# haasoscope_pro_fpga_board_-_start_of_io.net
KiCad netlist of a schematic drawn in EAGLE
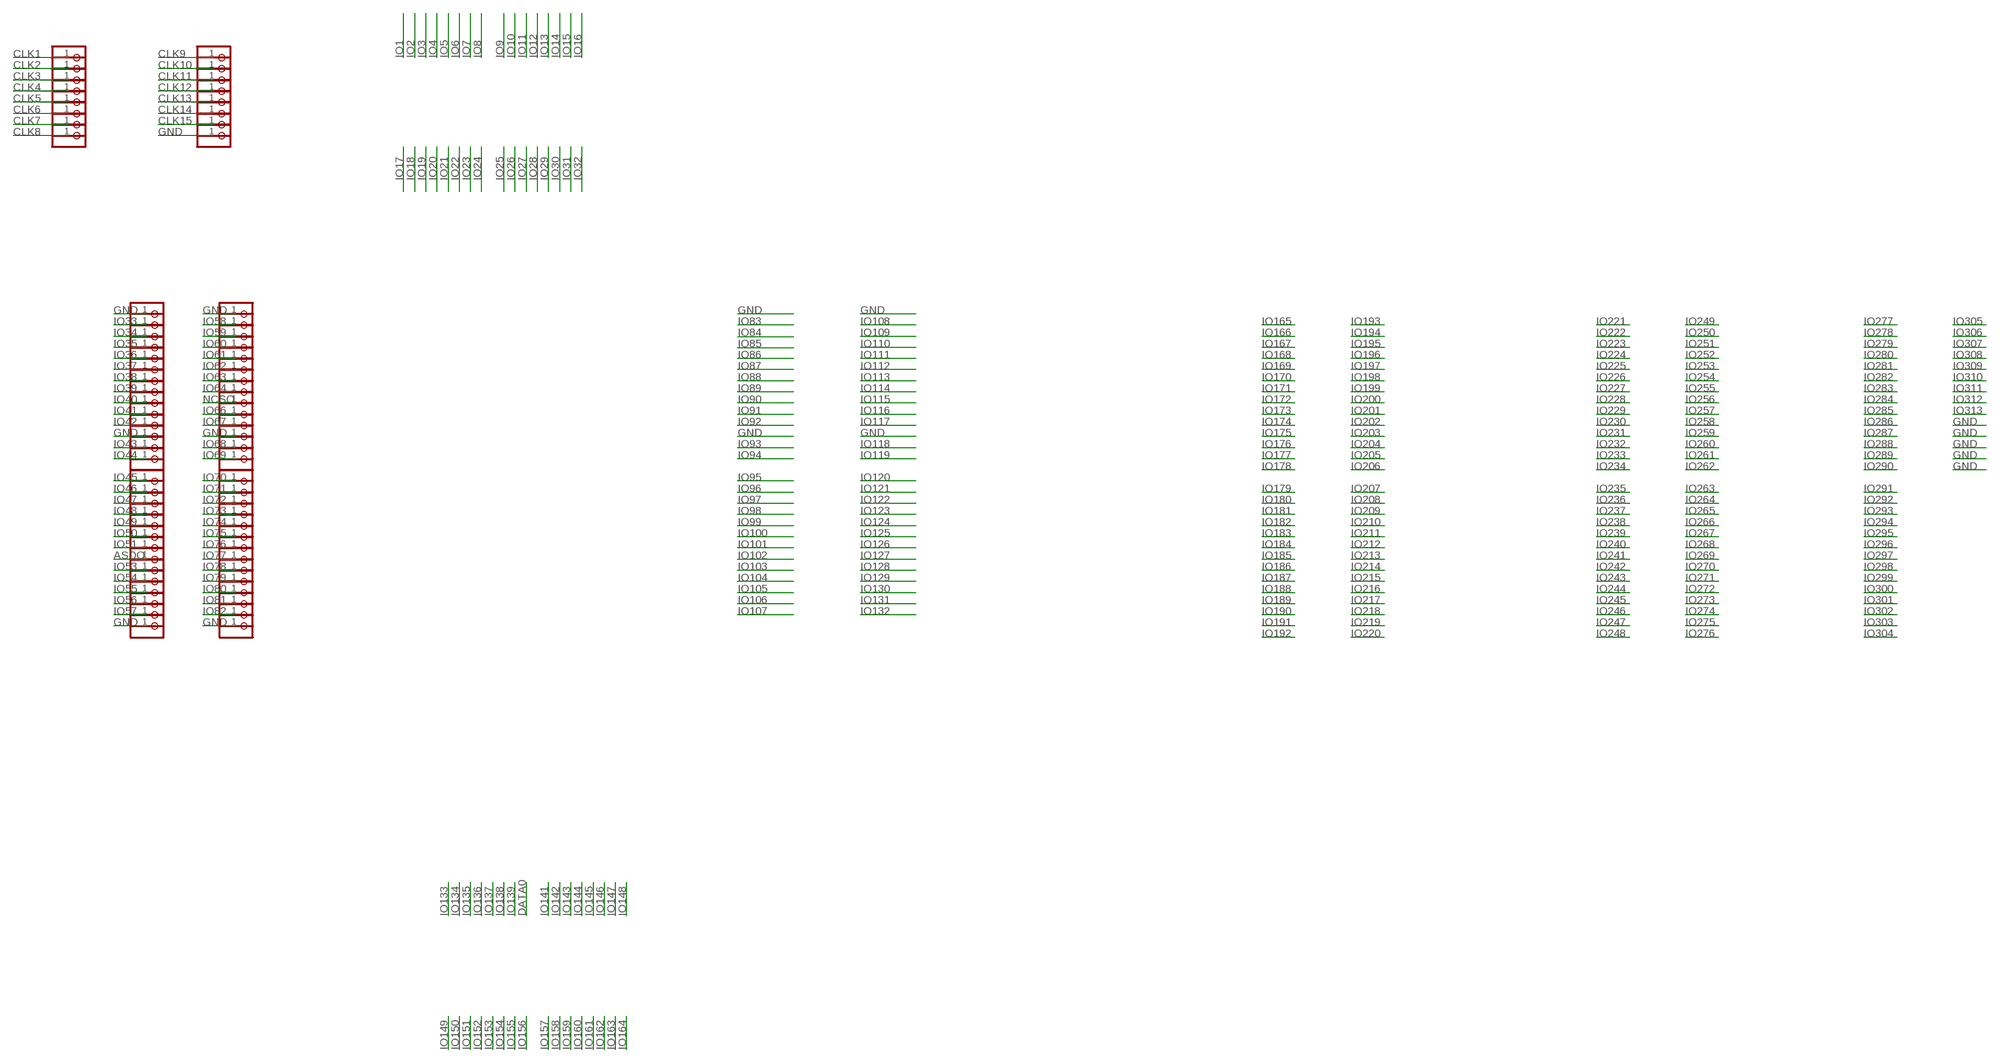
[diagram p0: schematic, sheet 1]
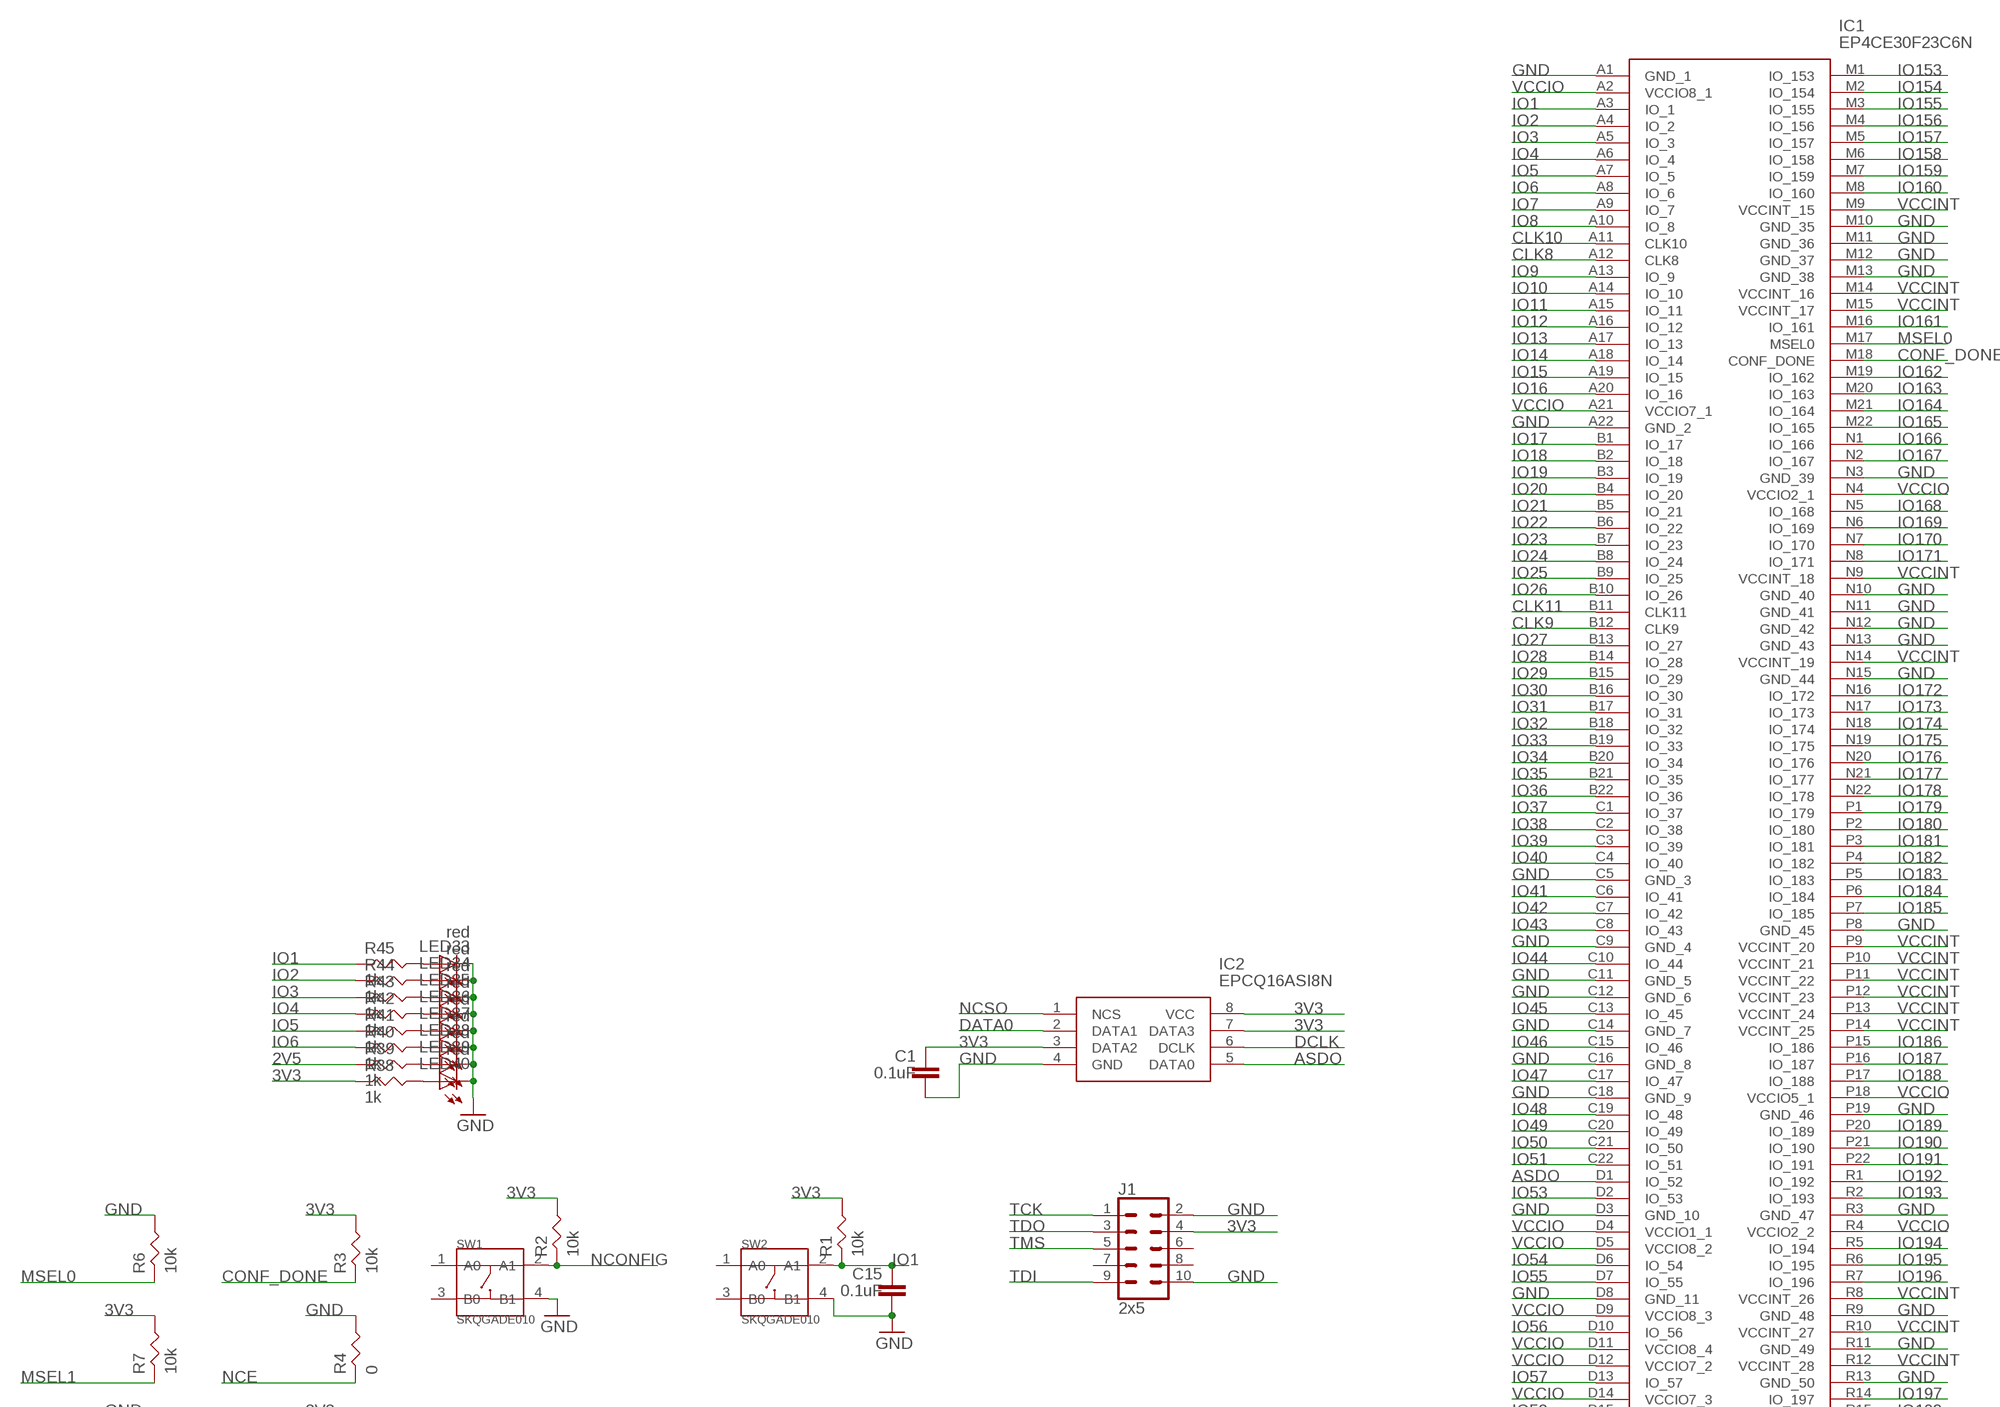
[diagram p1: schematic, sheet 2, part 1 of 2]
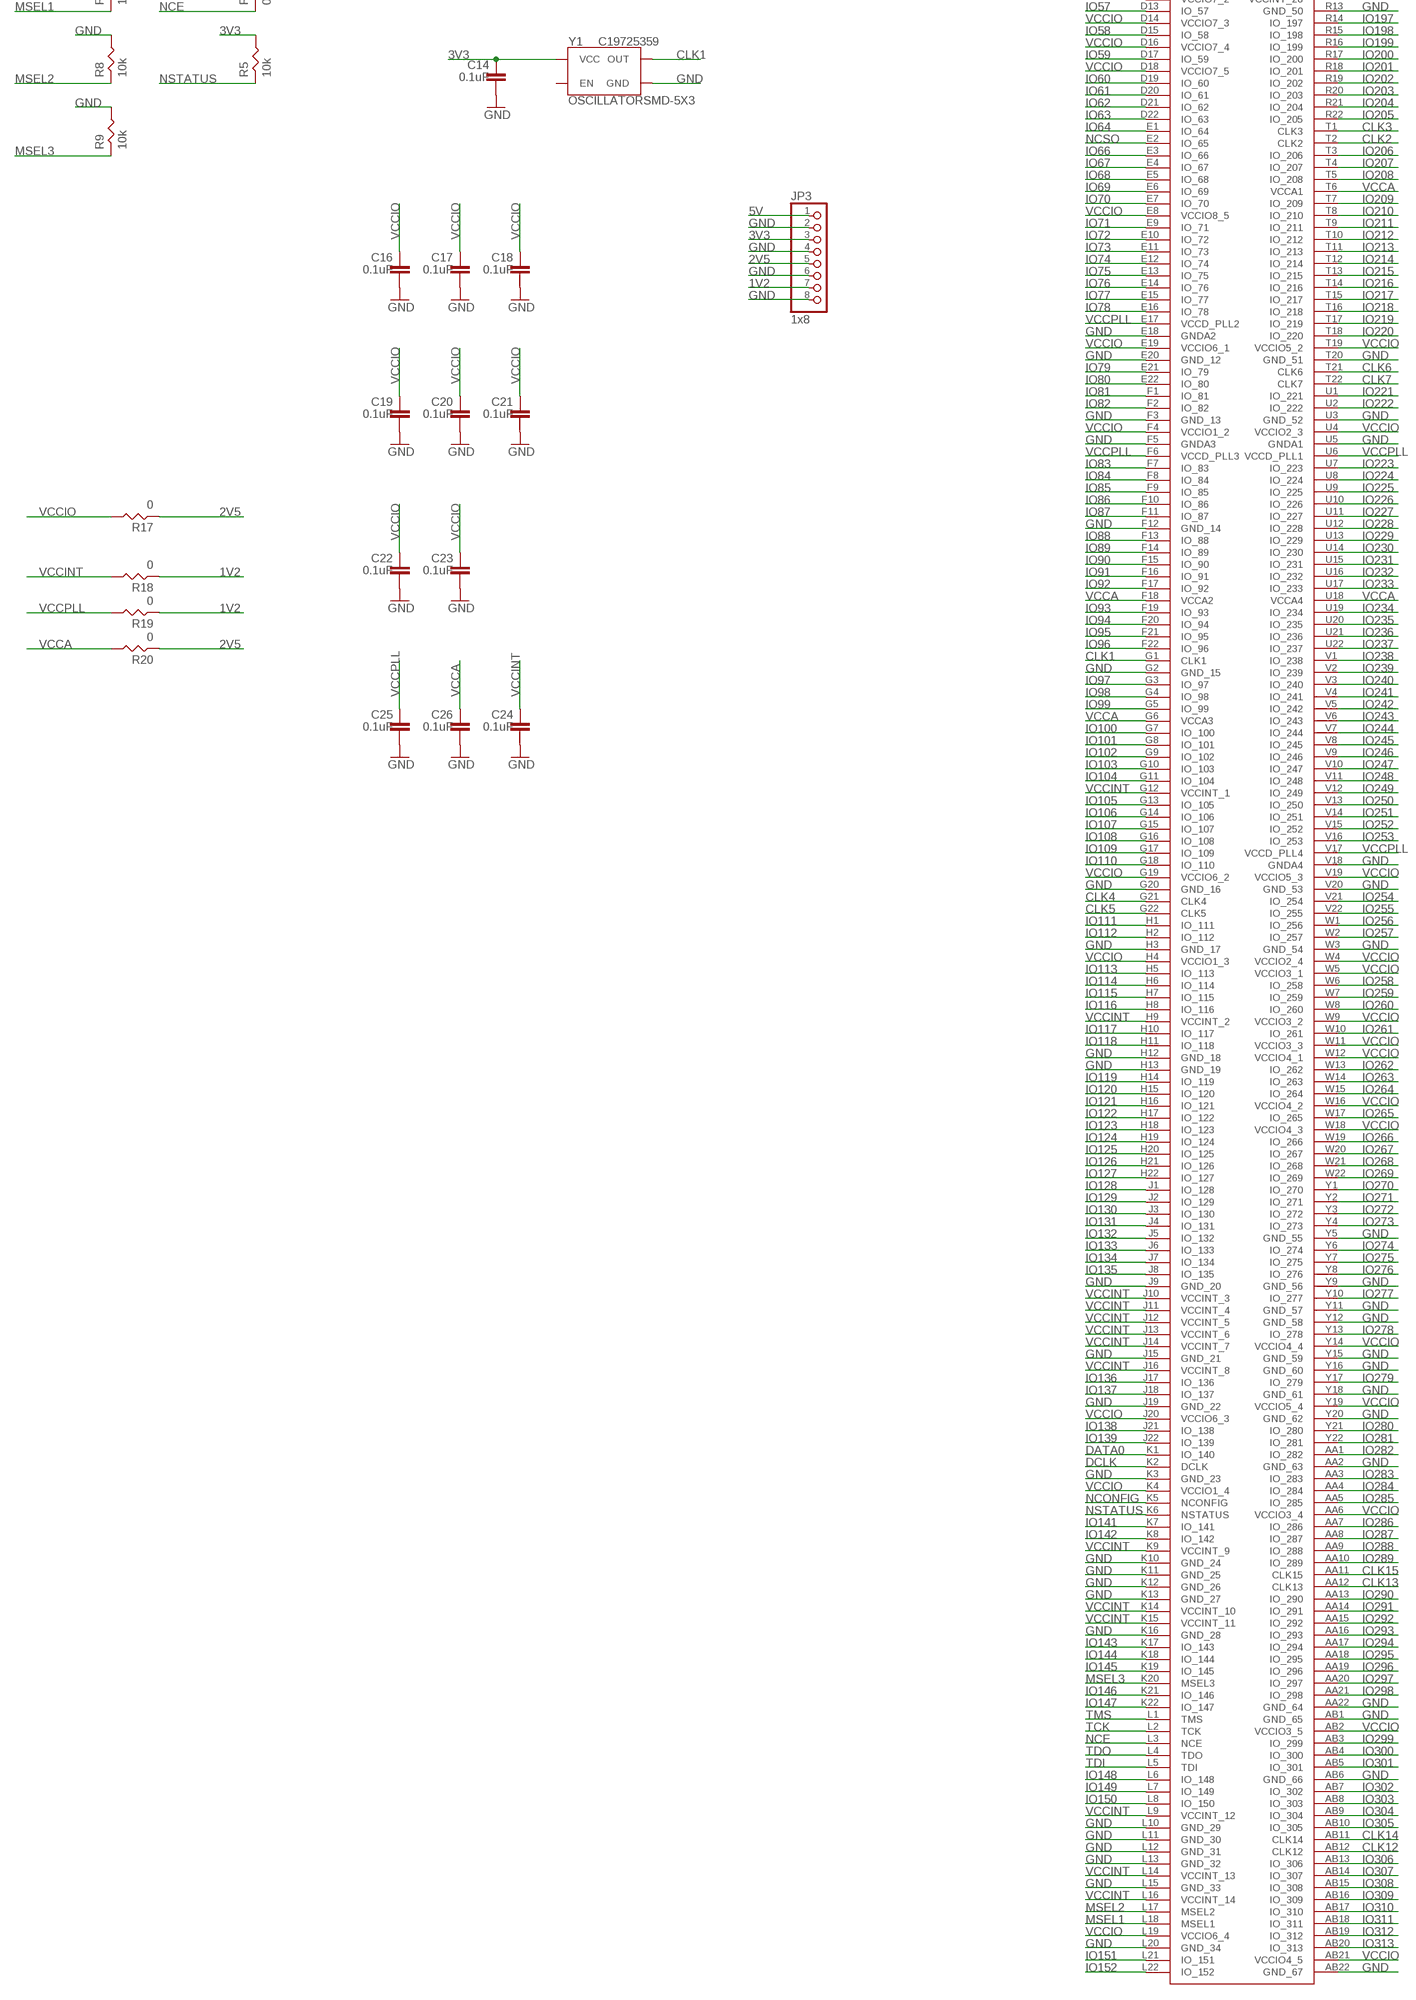
[diagram p2: schematic, sheet 2, part 2 of 2]
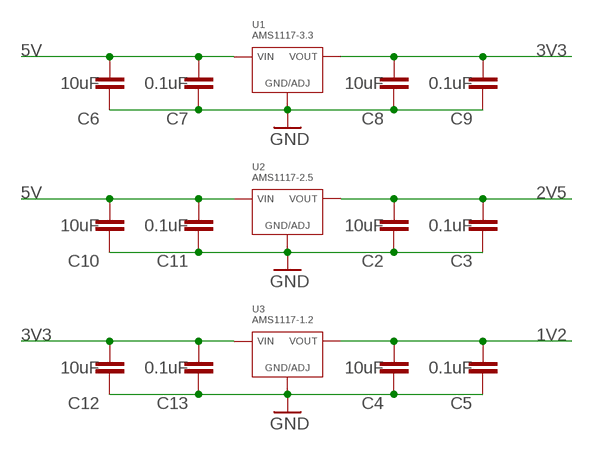
[diagram p3: schematic, sheet 3]

(export (version "E")
  (design (tool "Eeschema 10.0.6"))
  (components
    (comp (ref "C2")
      (value "10uF")
      (footprint "eagle-import:RESC0805_N")
      (libsource (lib "eagle-import") (part "CAPACITOR_0805_N"))
    )
    (comp (ref "C3")
      (value "0.1uF")
      (footprint "eagle-import:RESC0402_N")
      (libsource (lib "eagle-import") (part "CAPACITOR_0402_N"))
    )
    (comp (ref "C4")
      (value "10uF")
      (footprint "eagle-import:RESC0805_N")
      (libsource (lib "eagle-import") (part "CAPACITOR_0805_N"))
    )
    (comp (ref "C5")
      (value "0.1uF")
      (footprint "eagle-import:RESC0402_N")
      (libsource (lib "eagle-import") (part "CAPACITOR_0402_N"))
    )
    (comp (ref "C6")
      (value "10uF")
      (footprint "eagle-import:RESC0805_N")
      (libsource (lib "eagle-import") (part "CAPACITOR_0805_N"))
    )
    (comp (ref "C7")
      (value "0.1uF")
      (footprint "eagle-import:RESC0402_N")
      (libsource (lib "eagle-import") (part "CAPACITOR_0402_N"))
    )
    (comp (ref "C8")
      (value "10uF")
      (footprint "eagle-import:RESC0805_N")
      (libsource (lib "eagle-import") (part "CAPACITOR_0805_N"))
    )
    (comp (ref "C9")
      (value "0.1uF")
      (footprint "eagle-import:RESC0402_N")
      (libsource (lib "eagle-import") (part "CAPACITOR_0402_N"))
    )
    (comp (ref "C10")
      (value "10uF")
      (footprint "eagle-import:RESC0805_N")
      (libsource (lib "eagle-import") (part "CAPACITOR_0805_N"))
    )
    (comp (ref "C11")
      (value "0.1uF")
      (footprint "eagle-import:RESC0402_N")
      (libsource (lib "eagle-import") (part "CAPACITOR_0402_N"))
    )
    (comp (ref "C12")
      (value "10uF")
      (footprint "eagle-import:RESC0805_N")
      (libsource (lib "eagle-import") (part "CAPACITOR_0805_N"))
    )
    (comp (ref "C13")
      (value "0.1uF")
      (footprint "eagle-import:RESC0402_N")
      (libsource (lib "eagle-import") (part "CAPACITOR_0402_N"))
    )
    (comp (ref "U1")
      (value "AMS1117-3.3")
      (footprint "eagle-import:SOT-223-3")
      (fields
        (field (name "HOUSEPART") "NO")
        (field (name "MPN") "NCP1117LPST33T3G")
        (field (name "MPN_1") "AMS1117-3.3")
      )
      (libsource (lib "eagle-import") (part "NCP1117LPST33T3G"))
    )
    (comp (ref "U2")
      (value "AMS1117-2.5")
      (footprint "eagle-import:SOT-223-3")
      (fields
        (field (name "HOUSEPART") "NO")
        (field (name "MPN") "NCP1117LPST33T3G")
        (field (name "MPN_1") "AMS1117-2.5")
      )
      (libsource (lib "eagle-import") (part "NCP1117LPST33T3G"))
    )
    (comp (ref "U3")
      (value "AMS1117-1.2")
      (footprint "eagle-import:SOT-223-3")
      (fields
        (field (name "HOUSEPART") "NO")
        (field (name "MPN") "NCP1117LPST33T3G")
        (field (name "MPN_1") "AMS1117-1.2")
      )
      (libsource (lib "eagle-import") (part "NCP1117LPST33T3G"))
    )
    (comp (ref "JP1")
      (value "1")
      (footprint "eagle-import:1X01")
      (libsource (lib "eagle-import") (part "PINHD-1X1"))
    )
    (comp (ref "JP2")
      (value "1")
      (footprint "eagle-import:1X01")
      (libsource (lib "eagle-import") (part "PINHD-1X1"))
    )
    (comp (ref "JP4")
      (value "1")
      (footprint "eagle-import:1X01")
      (libsource (lib "eagle-import") (part "PINHD-1X1"))
    )
    (comp (ref "JP5")
      (value "1")
      (footprint "eagle-import:1X01")
      (libsource (lib "eagle-import") (part "PINHD-1X1"))
    )
    (comp (ref "JP6")
      (value "1")
      (footprint "eagle-import:1X01")
      (libsource (lib "eagle-import") (part "PINHD-1X1"))
    )
    (comp (ref "JP7")
      (value "1")
      (footprint "eagle-import:1X01")
      (libsource (lib "eagle-import") (part "PINHD-1X1"))
    )
    (comp (ref "JP8")
      (value "1")
      (footprint "eagle-import:1X01")
      (libsource (lib "eagle-import") (part "PINHD-1X1"))
    )
    (comp (ref "JP9")
      (value "1")
      (footprint "eagle-import:1X01")
      (libsource (lib "eagle-import") (part "PINHD-1X1"))
    )
    (comp (ref "JP10")
      (value "1")
      (footprint "eagle-import:1X01")
      (libsource (lib "eagle-import") (part "PINHD-1X1"))
    )
    (comp (ref "JP11")
      (value "1")
      (footprint "eagle-import:1X01")
      (libsource (lib "eagle-import") (part "PINHD-1X1"))
    )
    (comp (ref "JP12")
      (value "1")
      (footprint "eagle-import:1X01")
      (libsource (lib "eagle-import") (part "PINHD-1X1"))
    )
    (comp (ref "JP13")
      (value "1")
      (footprint "eagle-import:1X01")
      (libsource (lib "eagle-import") (part "PINHD-1X1"))
    )
    (comp (ref "JP14")
      (value "1")
      (footprint "eagle-import:1X01")
      (libsource (lib "eagle-import") (part "PINHD-1X1"))
    )
    (comp (ref "JP15")
      (value "1")
      (footprint "eagle-import:1X01")
      (libsource (lib "eagle-import") (part "PINHD-1X1"))
    )
    (comp (ref "JP16")
      (value "1")
      (footprint "eagle-import:1X01")
      (libsource (lib "eagle-import") (part "PINHD-1X1"))
    )
    (comp (ref "JP17")
      (value "1")
      (footprint "eagle-import:1X01")
      (libsource (lib "eagle-import") (part "PINHD-1X1"))
    )
    (comp (ref "JP18")
      (value "1")
      (footprint "eagle-import:1X01")
      (libsource (lib "eagle-import") (part "PINHD-1X1"))
    )
    (comp (ref "JP19")
      (value "1")
      (footprint "eagle-import:1X01")
      (libsource (lib "eagle-import") (part "PINHD-1X1"))
    )
    (comp (ref "JP20")
      (value "1")
      (footprint "eagle-import:1X01")
      (libsource (lib "eagle-import") (part "PINHD-1X1"))
    )
    (comp (ref "JP21")
      (value "1")
      (footprint "eagle-import:1X01")
      (libsource (lib "eagle-import") (part "PINHD-1X1"))
    )
    (comp (ref "JP22")
      (value "1")
      (footprint "eagle-import:1X01")
      (libsource (lib "eagle-import") (part "PINHD-1X1"))
    )
    (comp (ref "JP23")
      (value "1")
      (footprint "eagle-import:1X01")
      (libsource (lib "eagle-import") (part "PINHD-1X1"))
    )
    (comp (ref "JP24")
      (value "1")
      (footprint "eagle-import:1X01")
      (libsource (lib "eagle-import") (part "PINHD-1X1"))
    )
    (comp (ref "JP25")
      (value "1")
      (footprint "eagle-import:1X01")
      (libsource (lib "eagle-import") (part "PINHD-1X1"))
    )
    (comp (ref "JP26")
      (value "1")
      (footprint "eagle-import:1X01")
      (libsource (lib "eagle-import") (part "PINHD-1X1"))
    )
    (comp (ref "JP27")
      (value "1")
      (footprint "eagle-import:1X01")
      (libsource (lib "eagle-import") (part "PINHD-1X1"))
    )
    (comp (ref "JP28")
      (value "1")
      (footprint "eagle-import:1X01")
      (libsource (lib "eagle-import") (part "PINHD-1X1"))
    )
    (comp (ref "JP29")
      (value "1")
      (footprint "eagle-import:1X01")
      (libsource (lib "eagle-import") (part "PINHD-1X1"))
    )
    (comp (ref "JP30")
      (value "1")
      (footprint "eagle-import:1X01")
      (libsource (lib "eagle-import") (part "PINHD-1X1"))
    )
    (comp (ref "JP31")
      (value "1")
      (footprint "eagle-import:1X01")
      (libsource (lib "eagle-import") (part "PINHD-1X1"))
    )
    (comp (ref "JP32")
      (value "1")
      (footprint "eagle-import:1X01")
      (libsource (lib "eagle-import") (part "PINHD-1X1"))
    )
    (comp (ref "JP33")
      (value "1")
      (footprint "eagle-import:1X01")
      (libsource (lib "eagle-import") (part "PINHD-1X1"))
    )
    (comp (ref "JP34")
      (value "1")
      (footprint "eagle-import:1X01")
      (libsource (lib "eagle-import") (part "PINHD-1X1"))
    )
    (comp (ref "JP35")
      (value "1")
      (footprint "eagle-import:1X01")
      (libsource (lib "eagle-import") (part "PINHD-1X1"))
    )
    (comp (ref "JP36")
      (value "1")
      (footprint "eagle-import:1X01")
      (libsource (lib "eagle-import") (part "PINHD-1X1"))
    )
    (comp (ref "JP37")
      (value "1")
      (footprint "eagle-import:1X01")
      (libsource (lib "eagle-import") (part "PINHD-1X1"))
    )
    (comp (ref "JP38")
      (value "1")
      (footprint "eagle-import:1X01")
      (libsource (lib "eagle-import") (part "PINHD-1X1"))
    )
    (comp (ref "JP39")
      (value "1")
      (footprint "eagle-import:1X01")
      (libsource (lib "eagle-import") (part "PINHD-1X1"))
    )
    (comp (ref "JP40")
      (value "1")
      (footprint "eagle-import:1X01")
      (libsource (lib "eagle-import") (part "PINHD-1X1"))
    )
    (comp (ref "JP41")
      (value "1")
      (footprint "eagle-import:1X01")
      (libsource (lib "eagle-import") (part "PINHD-1X1"))
    )
    (comp (ref "JP42")
      (value "1")
      (footprint "eagle-import:1X01")
      (libsource (lib "eagle-import") (part "PINHD-1X1"))
    )
    (comp (ref "JP43")
      (value "1")
      (footprint "eagle-import:1X01")
      (libsource (lib "eagle-import") (part "PINHD-1X1"))
    )
    (comp (ref "JP44")
      (value "1")
      (footprint "eagle-import:1X01")
      (libsource (lib "eagle-import") (part "PINHD-1X1"))
    )
    (comp (ref "JP45")
      (value "1")
      (footprint "eagle-import:1X01")
      (libsource (lib "eagle-import") (part "PINHD-1X1"))
    )
    (comp (ref "JP46")
      (value "1")
      (footprint "eagle-import:1X01")
      (libsource (lib "eagle-import") (part "PINHD-1X1"))
    )
    (comp (ref "JP47")
      (value "1")
      (footprint "eagle-import:1X01")
      (libsource (lib "eagle-import") (part "PINHD-1X1"))
    )
    (comp (ref "JP48")
      (value "1")
      (footprint "eagle-import:1X01")
      (libsource (lib "eagle-import") (part "PINHD-1X1"))
    )
    (comp (ref "JP49")
      (value "1")
      (footprint "eagle-import:1X01")
      (libsource (lib "eagle-import") (part "PINHD-1X1"))
    )
    (comp (ref "JP50")
      (value "1")
      (footprint "eagle-import:1X01")
      (libsource (lib "eagle-import") (part "PINHD-1X1"))
    )
    (comp (ref "JP51")
      (value "1")
      (footprint "eagle-import:1X01")
      (libsource (lib "eagle-import") (part "PINHD-1X1"))
    )
    (comp (ref "JP52")
      (value "1")
      (footprint "eagle-import:1X01")
      (libsource (lib "eagle-import") (part "PINHD-1X1"))
    )
    (comp (ref "JP53")
      (value "1")
      (footprint "eagle-import:1X01")
      (libsource (lib "eagle-import") (part "PINHD-1X1"))
    )
    (comp (ref "JP54")
      (value "1")
      (footprint "eagle-import:1X01")
      (libsource (lib "eagle-import") (part "PINHD-1X1"))
    )
    (comp (ref "JP55")
      (value "1")
      (footprint "eagle-import:1X01")
      (libsource (lib "eagle-import") (part "PINHD-1X1"))
    )
    (comp (ref "JP56")
      (value "1")
      (footprint "eagle-import:1X01")
      (libsource (lib "eagle-import") (part "PINHD-1X1"))
    )
    (comp (ref "JP57")
      (value "1")
      (footprint "eagle-import:1X01")
      (libsource (lib "eagle-import") (part "PINHD-1X1"))
    )
    (comp (ref "JP58")
      (value "1")
      (footprint "eagle-import:1X01")
      (libsource (lib "eagle-import") (part "PINHD-1X1"))
    )
    (comp (ref "JP59")
      (value "1")
      (footprint "eagle-import:1X01")
      (libsource (lib "eagle-import") (part "PINHD-1X1"))
    )
    (comp (ref "JP60")
      (value "1")
      (footprint "eagle-import:1X01")
      (libsource (lib "eagle-import") (part "PINHD-1X1"))
    )
    (comp (ref "JP61")
      (value "1")
      (footprint "eagle-import:1X01")
      (libsource (lib "eagle-import") (part "PINHD-1X1"))
    )
    (comp (ref "JP62")
      (value "1")
      (footprint "eagle-import:1X01")
      (libsource (lib "eagle-import") (part "PINHD-1X1"))
    )
    (comp (ref "JP63")
      (value "1")
      (footprint "eagle-import:1X01")
      (libsource (lib "eagle-import") (part "PINHD-1X1"))
    )
    (comp (ref "JP64")
      (value "1")
      (footprint "eagle-import:1X01")
      (libsource (lib "eagle-import") (part "PINHD-1X1"))
    )
    (comp (ref "JP65")
      (value "1")
      (footprint "eagle-import:1X01")
      (libsource (lib "eagle-import") (part "PINHD-1X1"))
    )
    (comp (ref "JP66")
      (value "1")
      (footprint "eagle-import:1X01")
      (libsource (lib "eagle-import") (part "PINHD-1X1"))
    )
    (comp (ref "JP67")
      (value "1")
      (footprint "eagle-import:1X01")
      (libsource (lib "eagle-import") (part "PINHD-1X1"))
    )
    (comp (ref "JP68")
      (value "1")
      (footprint "eagle-import:1X01")
      (libsource (lib "eagle-import") (part "PINHD-1X1"))
    )
    (comp (ref "JP69")
      (value "1")
      (footprint "eagle-import:1X01")
      (libsource (lib "eagle-import") (part "PINHD-1X1"))
    )
    (comp (ref "JP70")
      (value "1")
      (footprint "eagle-import:1X01")
      (libsource (lib "eagle-import") (part "PINHD-1X1"))
    )
    (comp (ref "JP71")
      (value "1")
      (footprint "eagle-import:1X01")
      (libsource (lib "eagle-import") (part "PINHD-1X1"))
    )
    (comp (ref "JP72")
      (value "1")
      (footprint "eagle-import:1X01")
      (libsource (lib "eagle-import") (part "PINHD-1X1"))
    )
    (comp (ref "JP73")
      (value "1")
      (footprint "eagle-import:1X01")
      (libsource (lib "eagle-import") (part "PINHD-1X1"))
    )
    (comp (ref "C1")
      (value "0.1uF")
      (footprint "eagle-import:RESC0402_N")
      (libsource (lib "eagle-import") (part "CAPACITOR_0402_N"))
    )
    (comp (ref "C14")
      (value "0.1uF")
      (footprint "eagle-import:RESC0402_N")
      (libsource (lib "eagle-import") (part "CAPACITOR_0402_N"))
    )
    (comp (ref "C15")
      (value "0.1uF")
      (footprint "eagle-import:RESC0402_N")
      (libsource (lib "eagle-import") (part "CAPACITOR_0402_N"))
    )
    (comp (ref "C16")
      (value "0.1uF")
      (footprint "eagle-import:RESC0402_N")
      (libsource (lib "eagle-import") (part "CAPACITOR_0402_N"))
    )
    (comp (ref "C17")
      (value "0.1uF")
      (footprint "eagle-import:RESC0402_N")
      (libsource (lib "eagle-import") (part "CAPACITOR_0402_N"))
    )
    (comp (ref "C18")
      (value "0.1uF")
      (footprint "eagle-import:RESC0402_N")
      (libsource (lib "eagle-import") (part "CAPACITOR_0402_N"))
    )
    (comp (ref "C19")
      (value "0.1uF")
      (footprint "eagle-import:RESC0402_N")
      (libsource (lib "eagle-import") (part "CAPACITOR_0402_N"))
    )
    (comp (ref "C20")
      (value "0.1uF")
      (footprint "eagle-import:RESC0402_N")
      (libsource (lib "eagle-import") (part "CAPACITOR_0402_N"))
    )
    (comp (ref "C21")
      (value "0.1uF")
      (footprint "eagle-import:RESC0402_N")
      (libsource (lib "eagle-import") (part "CAPACITOR_0402_N"))
    )
    (comp (ref "C22")
      (value "0.1uF")
      (footprint "eagle-import:RESC0402_N")
      (libsource (lib "eagle-import") (part "CAPACITOR_0402_N"))
    )
    (comp (ref "C23")
      (value "0.1uF")
      (footprint "eagle-import:RESC0402_N")
      (libsource (lib "eagle-import") (part "CAPACITOR_0402_N"))
    )
    (comp (ref "C24")
      (value "0.1uF")
      (footprint "eagle-import:RESC0402_N")
      (libsource (lib "eagle-import") (part "CAPACITOR_0402_N"))
    )
    (comp (ref "C25")
      (value "0.1uF")
      (footprint "eagle-import:RESC0402_N")
      (libsource (lib "eagle-import") (part "CAPACITOR_0402_N"))
    )
    (comp (ref "C26")
      (value "0.1uF")
      (footprint "eagle-import:RESC0402_N")
      (libsource (lib "eagle-import") (part "CAPACITOR_0402_N"))
    )
    (comp (ref "IC1")
      (value "EP4CE30F23C6N")
      (footprint "eagle-import:BGA484C100P22X22_2300X2300X240")
      (fields (field (name "MOUSER_PART_NUMBER") "989-EP4CE30F23C6N"))
      (libsource (lib "eagle-import") (part "EP4CE30F23C6N"))
    )
    (comp (ref "IC2")
      (value "EPCQ16ASI8N")
      (footprint "eagle-import:SOIC127P600X175-8N")
      (fields (field (name "MOUSER_PART_NUMBER") "989-EPCQ16ASI8N"))
      (libsource (lib "eagle-import") (part "EPCQ16ASI8N"))
    )
    (comp (ref "J1")
      (value "2x5")
      (footprint "eagle-import:2X5-SHROUDED")
      (libsource (lib "eagle-import") (part "CONN_05X2SHD"))
    )
    (comp (ref "JP3")
      (value "1x8")
      (footprint "eagle-import:1X08")
      (libsource (lib "eagle-import") (part "PINHD-1X8"))
    )
    (comp (ref "LED33")
      (value "red")
      (footprint "eagle-import:CHIP-LED0603")
      (libsource (lib "eagle-import") (part "LEDCHIP-LED0603"))
    )
    (comp (ref "LED34")
      (value "red")
      (footprint "eagle-import:CHIP-LED0603")
      (libsource (lib "eagle-import") (part "LEDCHIP-LED0603"))
    )
    (comp (ref "LED35")
      (value "red")
      (footprint "eagle-import:CHIP-LED0603")
      (libsource (lib "eagle-import") (part "LEDCHIP-LED0603"))
    )
    (comp (ref "LED36")
      (value "red")
      (footprint "eagle-import:CHIP-LED0603")
      (libsource (lib "eagle-import") (part "LEDCHIP-LED0603"))
    )
    (comp (ref "LED37")
      (value "red")
      (footprint "eagle-import:CHIP-LED0603")
      (libsource (lib "eagle-import") (part "LEDCHIP-LED0603"))
    )
    (comp (ref "LED38")
      (value "red")
      (footprint "eagle-import:CHIP-LED0603")
      (libsource (lib "eagle-import") (part "LEDCHIP-LED0603"))
    )
    (comp (ref "LED39")
      (value "red")
      (footprint "eagle-import:CHIP-LED0603")
      (libsource (lib "eagle-import") (part "LEDCHIP-LED0603"))
    )
    (comp (ref "LED40")
      (value "red")
      (footprint "eagle-import:CHIP-LED0603")
      (libsource (lib "eagle-import") (part "LEDCHIP-LED0603"))
    )
    (comp (ref "R1")
      (value "10k")
      (footprint "eagle-import:RES-0402")
      (libsource (lib "eagle-import") (part "RES-0402"))
    )
    (comp (ref "R2")
      (value "10k")
      (footprint "eagle-import:RES-0402")
      (libsource (lib "eagle-import") (part "RES-0402"))
    )
    (comp (ref "R3")
      (value "10k")
      (footprint "eagle-import:RES-0402")
      (libsource (lib "eagle-import") (part "RES-0402"))
    )
    (comp (ref "R4")
      (value "0")
      (footprint "eagle-import:RES-0402")
      (libsource (lib "eagle-import") (part "RES-0402"))
    )
    (comp (ref "R5")
      (value "10k")
      (footprint "eagle-import:RES-0402")
      (libsource (lib "eagle-import") (part "RES-0402"))
    )
    (comp (ref "R6")
      (value "10k")
      (footprint "eagle-import:RES-0402")
      (libsource (lib "eagle-import") (part "RES-0402"))
    )
    (comp (ref "R7")
      (value "10k")
      (footprint "eagle-import:RES-0402")
      (libsource (lib "eagle-import") (part "RES-0402"))
    )
    (comp (ref "R8")
      (value "10k")
      (footprint "eagle-import:RES-0402")
      (libsource (lib "eagle-import") (part "RES-0402"))
    )
    (comp (ref "R9")
      (value "10k")
      (footprint "eagle-import:RES-0402")
      (libsource (lib "eagle-import") (part "RES-0402"))
    )
    (comp (ref "R17")
      (value "0")
      (footprint "eagle-import:RES-0402")
      (libsource (lib "eagle-import") (part "RES-0402"))
    )
    (comp (ref "R18")
      (value "0")
      (footprint "eagle-import:RES-0402")
      (libsource (lib "eagle-import") (part "RES-0402"))
    )
    (comp (ref "R19")
      (value "0")
      (footprint "eagle-import:RES-0402")
      (libsource (lib "eagle-import") (part "RES-0402"))
    )
    (comp (ref "R20")
      (value "0")
      (footprint "eagle-import:RES-0402")
      (libsource (lib "eagle-import") (part "RES-0402"))
    )
    (comp (ref "R38")
      (value "1k")
      (footprint "eagle-import:RES-0402")
      (libsource (lib "eagle-import") (part "RES-0402"))
    )
    (comp (ref "R39")
      (value "1k")
      (footprint "eagle-import:RES-0402")
      (libsource (lib "eagle-import") (part "RES-0402"))
    )
    (comp (ref "R40")
      (value "1k")
      (footprint "eagle-import:RES-0402")
      (libsource (lib "eagle-import") (part "RES-0402"))
    )
    (comp (ref "R41")
      (value "1k")
      (footprint "eagle-import:RES-0402")
      (libsource (lib "eagle-import") (part "RES-0402"))
    )
    (comp (ref "R42")
      (value "1k")
      (footprint "eagle-import:RES-0402")
      (libsource (lib "eagle-import") (part "RES-0402"))
    )
    (comp (ref "R43")
      (value "1k")
      (footprint "eagle-import:RES-0402")
      (libsource (lib "eagle-import") (part "RES-0402"))
    )
    (comp (ref "R44")
      (value "1k")
      (footprint "eagle-import:RES-0402")
      (libsource (lib "eagle-import") (part "RES-0402"))
    )
    (comp (ref "R45")
      (value "1k")
      (footprint "eagle-import:RES-0402")
      (libsource (lib "eagle-import") (part "RES-0402"))
    )
    (comp (ref "SW1")
      (value "SKQGADE010")
      (footprint "eagle-import:SW4-SMD-5.2X5.2X1.5MM")
      (libsource (lib "eagle-import") (part "SMD-BUTTON(4P-5.2X5.2X1.5MM-SKQGADE010)-SKQGADE010"))
    )
    (comp (ref "SW2")
      (value "SKQGADE010")
      (footprint "eagle-import:SW4-SMD-5.2X5.2X1.5MM")
      (libsource (lib "eagle-import") (part "SMD-BUTTON(4P-5.2X5.2X1.5MM-SKQGADE010)-SKQGADE010"))
    )
    (comp (ref "Y1")
      (value "OSCILLATORSMD-5X3")
      (footprint "eagle-import:OSCILLATOR-SMD-5X3.2")
      (fields (field (name "LCSC") "C19725359"))
      (libsource (lib "eagle-import") (part "OSCILLATORSMD-5X3"))
    )
  )
  (nets
    (net (code "1") (name "1V2") (class "Default")
      (node (ref "C4") (pin "2") (pinfunction "2_2") (pintype "passive"))
      (node (ref "C5") (pin "2") (pinfunction "2_2") (pintype "passive"))
      (node (ref "JP3") (pin "7") (pinfunction "7_7") (pintype "passive"))
      (node (ref "R18") (pin "P$1") (pinfunction "P$1_P$1") (pintype "bidirectional"))
      (node (ref "R19") (pin "P$1") (pinfunction "P$1_P$1") (pintype "bidirectional"))
      (node (ref "U3") (pin "P$1") (pinfunction "VOUT_P$1") (pintype "bidirectional"))
      (node (ref "U3") (pin "P$3") (pinfunction "VOUT_P$3") (pintype "bidirectional"))
    )
    (net (code "2") (name "2V5") (class "Default")
      (node (ref "C2") (pin "2") (pinfunction "2_2") (pintype "passive"))
      (node (ref "C3") (pin "2") (pinfunction "2_2") (pintype "passive"))
      (node (ref "JP3") (pin "5") (pinfunction "5_5") (pintype "passive"))
      (node (ref "R17") (pin "P$1") (pinfunction "P$1_P$1") (pintype "bidirectional"))
      (node (ref "R20") (pin "P$1") (pinfunction "P$1_P$1") (pintype "bidirectional"))
      (node (ref "R39") (pin "P$1") (pinfunction "P$1_P$1") (pintype "bidirectional"))
      (node (ref "U2") (pin "P$1") (pinfunction "VOUT_P$1") (pintype "bidirectional"))
      (node (ref "U2") (pin "P$3") (pinfunction "VOUT_P$3") (pintype "bidirectional"))
    )
    (net (code "3") (name "3V3") (class "Default")
      (node (ref "C1") (pin "2") (pinfunction "2_2") (pintype "passive"))
      (node (ref "C12") (pin "2") (pinfunction "2_2") (pintype "passive"))
      (node (ref "C13") (pin "2") (pinfunction "2_2") (pintype "passive"))
      (node (ref "C14") (pin "2") (pinfunction "2_2") (pintype "passive"))
      (node (ref "C8") (pin "2") (pinfunction "2_2") (pintype "passive"))
      (node (ref "C9") (pin "2") (pinfunction "2_2") (pintype "passive"))
      (node (ref "IC2") (pin "3") (pinfunction "DATA2_3") (pintype "bidirectional"))
      (node (ref "IC2") (pin "7") (pinfunction "DATA3_7") (pintype "bidirectional"))
      (node (ref "IC2") (pin "8") (pinfunction "VCC_8") (pintype "bidirectional"))
      (node (ref "J1") (pin "4") (pinfunction "4_4") (pintype "passive"))
      (node (ref "JP3") (pin "3") (pinfunction "3_3") (pintype "passive"))
      (node (ref "R1") (pin "P$2") (pinfunction "P$2_P$2") (pintype "bidirectional"))
      (node (ref "R2") (pin "P$2") (pinfunction "P$2_P$2") (pintype "bidirectional"))
      (node (ref "R3") (pin "P$2") (pinfunction "P$2_P$2") (pintype "bidirectional"))
      (node (ref "R38") (pin "P$1") (pinfunction "P$1_P$1") (pintype "bidirectional"))
      (node (ref "R5") (pin "P$2") (pinfunction "P$2_P$2") (pintype "bidirectional"))
      (node (ref "R7") (pin "P$2") (pinfunction "P$2_P$2") (pintype "bidirectional"))
      (node (ref "U1") (pin "P$1") (pinfunction "VOUT_P$1") (pintype "bidirectional"))
      (node (ref "U1") (pin "P$3") (pinfunction "VOUT_P$3") (pintype "bidirectional"))
      (node (ref "U3") (pin "P$4") (pinfunction "VIN_P$4") (pintype "bidirectional"))
      (node (ref "Y1") (pin "4") (pinfunction "VCC_4") (pintype "bidirectional"))
    )
    (net (code "4") (name "5V") (class "Default")
      (node (ref "C10") (pin "2") (pinfunction "2_2") (pintype "passive"))
      (node (ref "C11") (pin "2") (pinfunction "2_2") (pintype "passive"))
      (node (ref "C6") (pin "2") (pinfunction "2_2") (pintype "passive"))
      (node (ref "C7") (pin "2") (pinfunction "2_2") (pintype "passive"))
      (node (ref "JP3") (pin "1") (pinfunction "1_1") (pintype "passive"))
      (node (ref "U1") (pin "P$4") (pinfunction "VIN_P$4") (pintype "bidirectional"))
      (node (ref "U2") (pin "P$4") (pinfunction "VIN_P$4") (pintype "bidirectional"))
    )
    (net (code "5") (name "ASDO") (class "Default")
      (node (ref "IC1") (pin "D1") (pinfunction "IO_52_D1") (pintype "bidirectional"))
      (node (ref "IC2") (pin "5") (pinfunction "DATA0_5") (pintype "bidirectional"))
      (node (ref "JP39") (pin "1") (pinfunction "1_1") (pintype "passive"))
    )
    (net (code "6") (name "CLK1") (class "Default")
      (node (ref "IC1") (pin "G1") (pinfunction "CLK1_G1") (pintype "bidirectional"))
      (node (ref "JP16") (pin "1") (pinfunction "1_1") (pintype "passive"))
      (node (ref "Y1") (pin "3") (pinfunction "OUT_3") (pintype "bidirectional"))
    )
    (net (code "7") (name "CLK2") (class "Default")
      (node (ref "IC1") (pin "T2") (pinfunction "CLK2_T2") (pintype "bidirectional"))
      (node (ref "JP18") (pin "1") (pinfunction "1_1") (pintype "passive"))
    )
    (net (code "8") (name "CLK3") (class "Default")
      (node (ref "IC1") (pin "T1") (pinfunction "CLK3_T1") (pintype "bidirectional"))
      (node (ref "JP17") (pin "1") (pinfunction "1_1") (pintype "passive"))
    )
    (net (code "9") (name "CLK4") (class "Default")
      (node (ref "IC1") (pin "G21") (pinfunction "CLK4_G21") (pintype "bidirectional"))
      (node (ref "JP19") (pin "1") (pinfunction "1_1") (pintype "passive"))
    )
    (net (code "10") (name "CLK5") (class "Default")
      (node (ref "IC1") (pin "G22") (pinfunction "CLK5_G22") (pintype "bidirectional"))
      (node (ref "JP20") (pin "1") (pinfunction "1_1") (pintype "passive"))
    )
    (net (code "11") (name "CLK6") (class "Default")
      (node (ref "IC1") (pin "T21") (pinfunction "CLK6_T21") (pintype "bidirectional"))
      (node (ref "JP22") (pin "1") (pinfunction "1_1") (pintype "passive"))
    )
    (net (code "12") (name "CLK7") (class "Default")
      (node (ref "IC1") (pin "T22") (pinfunction "CLK7_T22") (pintype "bidirectional"))
      (node (ref "JP21") (pin "1") (pinfunction "1_1") (pintype "passive"))
    )
    (net (code "13") (name "CLK8") (class "Default")
      (node (ref "IC1") (pin "A12") (pinfunction "CLK8_A12") (pintype "bidirectional"))
      (node (ref "JP23") (pin "1") (pinfunction "1_1") (pintype "passive"))
    )
    (net (code "14") (name "CLK9") (class "Default")
      (node (ref "IC1") (pin "B12") (pinfunction "CLK9_B12") (pintype "bidirectional"))
      (node (ref "JP24") (pin "1") (pinfunction "1_1") (pintype "passive"))
    )
    (net (code "15") (name "CLK10") (class "Default")
      (node (ref "IC1") (pin "A11") (pinfunction "CLK10_A11") (pintype "bidirectional"))
      (node (ref "JP26") (pin "1") (pinfunction "1_1") (pintype "passive"))
    )
    (net (code "16") (name "CLK11") (class "Default")
      (node (ref "IC1") (pin "B11") (pinfunction "CLK11_B11") (pintype "bidirectional"))
      (node (ref "JP25") (pin "1") (pinfunction "1_1") (pintype "passive"))
    )
    (net (code "17") (name "CLK12") (class "Default")
      (node (ref "IC1") (pin "AB12") (pinfunction "CLK12_AB12") (pintype "bidirectional"))
      (node (ref "JP27") (pin "1") (pinfunction "1_1") (pintype "passive"))
    )
    (net (code "18") (name "CLK13") (class "Default")
      (node (ref "IC1") (pin "AA12") (pinfunction "CLK13_AA12") (pintype "bidirectional"))
      (node (ref "JP28") (pin "1") (pinfunction "1_1") (pintype "passive"))
    )
    (net (code "19") (name "CLK14") (class "Default")
      (node (ref "IC1") (pin "AB11") (pinfunction "CLK14_AB11") (pintype "bidirectional"))
      (node (ref "JP30") (pin "1") (pinfunction "1_1") (pintype "passive"))
    )
    (net (code "20") (name "CLK15") (class "Default")
      (node (ref "IC1") (pin "AA11") (pinfunction "CLK15_AA11") (pintype "bidirectional"))
      (node (ref "JP29") (pin "1") (pinfunction "1_1") (pintype "passive"))
    )
    (net (code "21") (name "CONF_DONE") (class "Default")
      (node (ref "IC1") (pin "M18") (pinfunction "CONF_DONE_M18") (pintype "bidirectional"))
      (node (ref "R3") (pin "P$1") (pinfunction "P$1_P$1") (pintype "bidirectional"))
    )
    (net (code "22") (name "DATA0") (class "Default")
      (node (ref "IC1") (pin "K1") (pinfunction "IO_140_K1") (pintype "bidirectional"))
      (node (ref "IC2") (pin "2") (pinfunction "DATA1_2") (pintype "bidirectional"))
    )
    (net (code "23") (name "DCLK") (class "Default")
      (node (ref "IC1") (pin "K2") (pinfunction "DCLK_K2") (pintype "bidirectional"))
      (node (ref "IC2") (pin "6") (pinfunction "DCLK_6") (pintype "bidirectional"))
    )
    (net (code "24") (name "GND") (class "Default")
      (node (ref "C1") (pin "1") (pinfunction "1_1") (pintype "passive"))
      (node (ref "C10") (pin "1") (pinfunction "1_1") (pintype "passive"))
      (node (ref "C11") (pin "1") (pinfunction "1_1") (pintype "passive"))
      (node (ref "C12") (pin "1") (pinfunction "1_1") (pintype "passive"))
      (node (ref "C13") (pin "1") (pinfunction "1_1") (pintype "passive"))
      (node (ref "C14") (pin "1") (pinfunction "1_1") (pintype "passive"))
      (node (ref "C15") (pin "1") (pinfunction "1_1") (pintype "passive"))
      (node (ref "C16") (pin "1") (pinfunction "1_1") (pintype "passive"))
      (node (ref "C17") (pin "1") (pinfunction "1_1") (pintype "passive"))
      (node (ref "C18") (pin "1") (pinfunction "1_1") (pintype "passive"))
      (node (ref "C19") (pin "1") (pinfunction "1_1") (pintype "passive"))
      (node (ref "C2") (pin "1") (pinfunction "1_1") (pintype "passive"))
      (node (ref "C20") (pin "1") (pinfunction "1_1") (pintype "passive"))
      (node (ref "C21") (pin "1") (pinfunction "1_1") (pintype "passive"))
      (node (ref "C22") (pin "1") (pinfunction "1_1") (pintype "passive"))
      (node (ref "C23") (pin "1") (pinfunction "1_1") (pintype "passive"))
      (node (ref "C24") (pin "1") (pinfunction "1_1") (pintype "passive"))
      (node (ref "C25") (pin "1") (pinfunction "1_1") (pintype "passive"))
      (node (ref "C26") (pin "1") (pinfunction "1_1") (pintype "passive"))
      (node (ref "C3") (pin "1") (pinfunction "1_1") (pintype "passive"))
      (node (ref "C4") (pin "1") (pinfunction "1_1") (pintype "passive"))
      (node (ref "C5") (pin "1") (pinfunction "1_1") (pintype "passive"))
      (node (ref "C6") (pin "1") (pinfunction "1_1") (pintype "passive"))
      (node (ref "C7") (pin "1") (pinfunction "1_1") (pintype "passive"))
      (node (ref "C8") (pin "1") (pinfunction "1_1") (pintype "passive"))
      (node (ref "C9") (pin "1") (pinfunction "1_1") (pintype "passive"))
      (node (ref "IC1") (pin "A1") (pinfunction "GND_1_A1") (pintype "bidirectional"))
      (node (ref "IC1") (pin "A22") (pinfunction "GND_2_A22") (pintype "bidirectional"))
      (node (ref "IC1") (pin "AA2") (pinfunction "GND_63_AA2") (pintype "bidirectional"))
      (node (ref "IC1") (pin "AA22") (pinfunction "GND_64_AA22") (pintype "bidirectional"))
      (node (ref "IC1") (pin "AB1") (pinfunction "GND_65_AB1") (pintype "bidirectional"))
      (node (ref "IC1") (pin "AB22") (pinfunction "GND_67_AB22") (pintype "bidirectional"))
      (node (ref "IC1") (pin "AB6") (pinfunction "GND_66_AB6") (pintype "bidirectional"))
      (node (ref "IC1") (pin "C11") (pinfunction "GND_5_C11") (pintype "bidirectional"))
      (node (ref "IC1") (pin "C12") (pinfunction "GND_6_C12") (pintype "bidirectional"))
      (node (ref "IC1") (pin "C14") (pinfunction "GND_7_C14") (pintype "bidirectional"))
      (node (ref "IC1") (pin "C16") (pinfunction "GND_8_C16") (pintype "bidirectional"))
      (node (ref "IC1") (pin "C18") (pinfunction "GND_9_C18") (pintype "bidirectional"))
      (node (ref "IC1") (pin "C5") (pinfunction "GND_3_C5") (pintype "bidirectional"))
      (node (ref "IC1") (pin "C9") (pinfunction "GND_4_C9") (pintype "bidirectional"))
      (node (ref "IC1") (pin "D3") (pinfunction "GND_10_D3") (pintype "bidirectional"))
      (node (ref "IC1") (pin "D8") (pinfunction "GND_11_D8") (pintype "bidirectional"))
      (node (ref "IC1") (pin "E18") (pinfunction "GNDA2_E18") (pintype "bidirectional"))
      (node (ref "IC1") (pin "E20") (pinfunction "GND_12_E20") (pintype "bidirectional"))
      (node (ref "IC1") (pin "F12") (pinfunction "GND_14_F12") (pintype "bidirectional"))
      (node (ref "IC1") (pin "F3") (pinfunction "GND_13_F3") (pintype "bidirectional"))
      (node (ref "IC1") (pin "F5") (pinfunction "GNDA3_F5") (pintype "bidirectional"))
      (node (ref "IC1") (pin "G2") (pinfunction "GND_15_G2") (pintype "bidirectional"))
      (node (ref "IC1") (pin "G20") (pinfunction "GND_16_G20") (pintype "bidirectional"))
      (node (ref "IC1") (pin "H12") (pinfunction "GND_18_H12") (pintype "bidirectional"))
      (node (ref "IC1") (pin "H13") (pinfunction "GND_19_H13") (pintype "bidirectional"))
      (node (ref "IC1") (pin "H3") (pinfunction "GND_17_H3") (pintype "bidirectional"))
      (node (ref "IC1") (pin "J15") (pinfunction "GND_21_J15") (pintype "bidirectional"))
      (node (ref "IC1") (pin "J19") (pinfunction "GND_22_J19") (pintype "bidirectional"))
      (node (ref "IC1") (pin "J9") (pinfunction "GND_20_J9") (pintype "bidirectional"))
      (node (ref "IC1") (pin "K10") (pinfunction "GND_24_K10") (pintype "bidirectional"))
      (node (ref "IC1") (pin "K11") (pinfunction "GND_25_K11") (pintype "bidirectional"))
      (node (ref "IC1") (pin "K12") (pinfunction "GND_26_K12") (pintype "bidirectional"))
      (node (ref "IC1") (pin "K13") (pinfunction "GND_27_K13") (pintype "bidirectional"))
      (node (ref "IC1") (pin "K16") (pinfunction "GND_28_K16") (pintype "bidirectional"))
      (node (ref "IC1") (pin "K3") (pinfunction "GND_23_K3") (pintype "bidirectional"))
      (node (ref "IC1") (pin "L10") (pinfunction "GND_29_L10") (pintype "bidirectional"))
      (node (ref "IC1") (pin "L11") (pinfunction "GND_30_L11") (pintype "bidirectional"))
      (node (ref "IC1") (pin "L12") (pinfunction "GND_31_L12") (pintype "bidirectional"))
      (node (ref "IC1") (pin "L13") (pinfunction "GND_32_L13") (pintype "bidirectional"))
      (node (ref "IC1") (pin "L15") (pinfunction "GND_33_L15") (pintype "bidirectional"))
      (node (ref "IC1") (pin "L20") (pinfunction "GND_34_L20") (pintype "bidirectional"))
      (node (ref "IC1") (pin "M10") (pinfunction "GND_35_M10") (pintype "bidirectional"))
      (node (ref "IC1") (pin "M11") (pinfunction "GND_36_M11") (pintype "bidirectional"))
      (node (ref "IC1") (pin "M12") (pinfunction "GND_37_M12") (pintype "bidirectional"))
      (node (ref "IC1") (pin "M13") (pinfunction "GND_38_M13") (pintype "bidirectional"))
      (node (ref "IC1") (pin "N10") (pinfunction "GND_40_N10") (pintype "bidirectional"))
      (node (ref "IC1") (pin "N11") (pinfunction "GND_41_N11") (pintype "bidirectional"))
      (node (ref "IC1") (pin "N12") (pinfunction "GND_42_N12") (pintype "bidirectional"))
      (node (ref "IC1") (pin "N13") (pinfunction "GND_43_N13") (pintype "bidirectional"))
      (node (ref "IC1") (pin "N15") (pinfunction "GND_44_N15") (pintype "bidirectional"))
      (node (ref "IC1") (pin "N3") (pinfunction "GND_39_N3") (pintype "bidirectional"))
      (node (ref "IC1") (pin "P19") (pinfunction "GND_46_P19") (pintype "bidirectional"))
      (node (ref "IC1") (pin "P8") (pinfunction "GND_45_P8") (pintype "bidirectional"))
      (node (ref "IC1") (pin "R11") (pinfunction "GND_49_R11") (pintype "bidirectional"))
      (node (ref "IC1") (pin "R13") (pinfunction "GND_50_R13") (pintype "bidirectional"))
      (node (ref "IC1") (pin "R3") (pinfunction "GND_47_R3") (pintype "bidirectional"))
      (node (ref "IC1") (pin "R9") (pinfunction "GND_48_R9") (pintype "bidirectional"))
      (node (ref "IC1") (pin "T20") (pinfunction "GND_51_T20") (pintype "bidirectional"))
      (node (ref "IC1") (pin "U3") (pinfunction "GND_52_U3") (pintype "bidirectional"))
      (node (ref "IC1") (pin "U5") (pinfunction "GNDA1_U5") (pintype "bidirectional"))
      (node (ref "IC1") (pin "V18") (pinfunction "GNDA4_V18") (pintype "bidirectional"))
      (node (ref "IC1") (pin "V20") (pinfunction "GND_53_V20") (pintype "bidirectional"))
      (node (ref "IC1") (pin "W3") (pinfunction "GND_54_W3") (pintype "bidirectional"))
      (node (ref "IC1") (pin "Y11") (pinfunction "GND_57_Y11") (pintype "bidirectional"))
      (node (ref "IC1") (pin "Y12") (pinfunction "GND_58_Y12") (pintype "bidirectional"))
      (node (ref "IC1") (pin "Y15") (pinfunction "GND_59_Y15") (pintype "bidirectional"))
      (node (ref "IC1") (pin "Y16") (pinfunction "GND_60_Y16") (pintype "bidirectional"))
      (node (ref "IC1") (pin "Y18") (pinfunction "GND_61_Y18") (pintype "bidirectional"))
      (node (ref "IC1") (pin "Y20") (pinfunction "GND_62_Y20") (pintype "bidirectional"))
      (node (ref "IC1") (pin "Y5") (pinfunction "GND_55_Y5") (pintype "bidirectional"))
      (node (ref "IC1") (pin "Y9") (pinfunction "GND_56_Y9") (pintype "bidirectional"))
      (node (ref "IC2") (pin "4") (pinfunction "GND_4") (pintype "bidirectional"))
      (node (ref "J1") (pin "10") (pinfunction "10_10") (pintype "passive"))
      (node (ref "J1") (pin "2") (pinfunction "2_2") (pintype "passive"))
      (node (ref "JP1") (pin "1") (pinfunction "1_1") (pintype "passive"))
      (node (ref "JP13") (pin "1") (pinfunction "1_1") (pintype "passive"))
      (node (ref "JP3") (pin "2") (pinfunction "2_2") (pintype "passive"))
      (node (ref "JP3") (pin "4") (pinfunction "4_4") (pintype "passive"))
      (node (ref "JP3") (pin "6") (pinfunction "6_6") (pintype "passive"))
      (node (ref "JP3") (pin "8") (pinfunction "8_8") (pintype "passive"))
      (node (ref "JP31") (pin "1") (pinfunction "1_1") (pintype "passive"))
      (node (ref "JP45") (pin "1") (pinfunction "1_1") (pintype "passive"))
      (node (ref "JP46") (pin "1") (pinfunction "1_1") (pintype "passive"))
      (node (ref "JP57") (pin "1") (pinfunction "1_1") (pintype "passive"))
      (node (ref "JP73") (pin "1") (pinfunction "1_1") (pintype "passive"))
      (node (ref "LED33") (pin "C") (pinfunction "C_C") (pintype "passive"))
      (node (ref "LED34") (pin "C") (pinfunction "C_C") (pintype "passive"))
      (node (ref "LED35") (pin "C") (pinfunction "C_C") (pintype "passive"))
      (node (ref "LED36") (pin "C") (pinfunction "C_C") (pintype "passive"))
      (node (ref "LED37") (pin "C") (pinfunction "C_C") (pintype "passive"))
      (node (ref "LED38") (pin "C") (pinfunction "C_C") (pintype "passive"))
      (node (ref "LED39") (pin "C") (pinfunction "C_C") (pintype "passive"))
      (node (ref "LED40") (pin "C") (pinfunction "C_C") (pintype "passive"))
      (node (ref "R4") (pin "P$2") (pinfunction "P$2_P$2") (pintype "bidirectional"))
      (node (ref "R6") (pin "P$2") (pinfunction "P$2_P$2") (pintype "bidirectional"))
      (node (ref "R8") (pin "P$2") (pinfunction "P$2_P$2") (pintype "bidirectional"))
      (node (ref "R9") (pin "P$2") (pinfunction "P$2_P$2") (pintype "bidirectional"))
      (node (ref "SW1") (pin "4") (pinfunction "B1_4") (pintype "bidirectional"))
      (node (ref "SW2") (pin "4") (pinfunction "B1_4") (pintype "bidirectional"))
      (node (ref "U1") (pin "P$2") (pinfunction "GND/ADJ_P$2") (pintype "bidirectional"))
      (node (ref "U2") (pin "P$2") (pinfunction "GND/ADJ_P$2") (pintype "bidirectional"))
      (node (ref "U3") (pin "P$2") (pinfunction "GND/ADJ_P$2") (pintype "bidirectional"))
      (node (ref "Y1") (pin "2") (pinfunction "GND_2") (pintype "bidirectional"))
    )
    (net (code "25") (name "IO1") (class "Default")
      (node (ref "C15") (pin "2") (pinfunction "2_2") (pintype "passive"))
      (node (ref "IC1") (pin "A3") (pinfunction "IO_1_A3") (pintype "bidirectional"))
      (node (ref "R1") (pin "P$1") (pinfunction "P$1_P$1") (pintype "bidirectional"))
      (node (ref "R45") (pin "P$1") (pinfunction "P$1_P$1") (pintype "bidirectional"))
      (node (ref "SW2") (pin "2") (pinfunction "A1_2") (pintype "bidirectional"))
    )
    (net (code "26") (name "IO2") (class "Default")
      (node (ref "IC1") (pin "A4") (pinfunction "IO_2_A4") (pintype "bidirectional"))
      (node (ref "R44") (pin "P$1") (pinfunction "P$1_P$1") (pintype "bidirectional"))
    )
    (net (code "27") (name "IO3") (class "Default")
      (node (ref "IC1") (pin "A5") (pinfunction "IO_3_A5") (pintype "bidirectional"))
      (node (ref "R43") (pin "P$1") (pinfunction "P$1_P$1") (pintype "bidirectional"))
    )
    (net (code "28") (name "IO4") (class "Default")
      (node (ref "IC1") (pin "A6") (pinfunction "IO_4_A6") (pintype "bidirectional"))
      (node (ref "R42") (pin "P$1") (pinfunction "P$1_P$1") (pintype "bidirectional"))
    )
    (net (code "29") (name "IO5") (class "Default")
      (node (ref "IC1") (pin "A7") (pinfunction "IO_5_A7") (pintype "bidirectional"))
      (node (ref "R41") (pin "P$1") (pinfunction "P$1_P$1") (pintype "bidirectional"))
    )
    (net (code "30") (name "IO6") (class "Default")
      (node (ref "IC1") (pin "A8") (pinfunction "IO_6_A8") (pintype "bidirectional"))
      (node (ref "R40") (pin "P$1") (pinfunction "P$1_P$1") (pintype "bidirectional"))
    )
    (net (code "31") (name "IO7") (class "Default")
      (node (ref "IC1") (pin "A9") (pinfunction "IO_7_A9") (pintype "bidirectional"))
    )
    (net (code "32") (name "IO8") (class "Default")
      (node (ref "IC1") (pin "A10") (pinfunction "IO_8_A10") (pintype "bidirectional"))
    )
    (net (code "33") (name "IO9") (class "Default")
      (node (ref "IC1") (pin "A13") (pinfunction "IO_9_A13") (pintype "bidirectional"))
    )
    (net (code "34") (name "IO10") (class "Default")
      (node (ref "IC1") (pin "A14") (pinfunction "IO_10_A14") (pintype "bidirectional"))
    )
    (net (code "35") (name "IO11") (class "Default")
      (node (ref "IC1") (pin "A15") (pinfunction "IO_11_A15") (pintype "bidirectional"))
    )
    (net (code "36") (name "IO12") (class "Default")
      (node (ref "IC1") (pin "A16") (pinfunction "IO_12_A16") (pintype "bidirectional"))
    )
    (net (code "37") (name "IO13") (class "Default")
      (node (ref "IC1") (pin "A17") (pinfunction "IO_13_A17") (pintype "bidirectional"))
    )
    (net (code "38") (name "IO14") (class "Default")
      (node (ref "IC1") (pin "A18") (pinfunction "IO_14_A18") (pintype "bidirectional"))
    )
    (net (code "39") (name "IO15") (class "Default")
      (node (ref "IC1") (pin "A19") (pinfunction "IO_15_A19") (pintype "bidirectional"))
    )
    (net (code "40") (name "IO16") (class "Default")
      (node (ref "IC1") (pin "A20") (pinfunction "IO_16_A20") (pintype "bidirectional"))
    )
    (net (code "41") (name "IO17") (class "Default")
      (node (ref "IC1") (pin "B1") (pinfunction "IO_17_B1") (pintype "bidirectional"))
    )
    (net (code "42") (name "IO18") (class "Default")
      (node (ref "IC1") (pin "B2") (pinfunction "IO_18_B2") (pintype "bidirectional"))
    )
    (net (code "43") (name "IO19") (class "Default")
      (node (ref "IC1") (pin "B3") (pinfunction "IO_19_B3") (pintype "bidirectional"))
    )
    (net (code "44") (name "IO20") (class "Default")
      (node (ref "IC1") (pin "B4") (pinfunction "IO_20_B4") (pintype "bidirectional"))
    )
    (net (code "45") (name "IO21") (class "Default")
      (node (ref "IC1") (pin "B5") (pinfunction "IO_21_B5") (pintype "bidirectional"))
    )
    (net (code "46") (name "IO22") (class "Default")
      (node (ref "IC1") (pin "B6") (pinfunction "IO_22_B6") (pintype "bidirectional"))
    )
    (net (code "47") (name "IO23") (class "Default")
      (node (ref "IC1") (pin "B7") (pinfunction "IO_23_B7") (pintype "bidirectional"))
    )
    (net (code "48") (name "IO24") (class "Default")
      (node (ref "IC1") (pin "B8") (pinfunction "IO_24_B8") (pintype "bidirectional"))
    )
    (net (code "49") (name "IO25") (class "Default")
      (node (ref "IC1") (pin "B9") (pinfunction "IO_25_B9") (pintype "bidirectional"))
    )
    (net (code "50") (name "IO26") (class "Default")
      (node (ref "IC1") (pin "B10") (pinfunction "IO_26_B10") (pintype "bidirectional"))
    )
    (net (code "51") (name "IO27") (class "Default")
      (node (ref "IC1") (pin "B13") (pinfunction "IO_27_B13") (pintype "bidirectional"))
    )
    (net (code "52") (name "IO28") (class "Default")
      (node (ref "IC1") (pin "B14") (pinfunction "IO_28_B14") (pintype "bidirectional"))
    )
    (net (code "53") (name "IO29") (class "Default")
      (node (ref "IC1") (pin "B15") (pinfunction "IO_29_B15") (pintype "bidirectional"))
    )
    (net (code "54") (name "IO30") (class "Default")
      (node (ref "IC1") (pin "B16") (pinfunction "IO_30_B16") (pintype "bidirectional"))
    )
    (net (code "55") (name "IO31") (class "Default")
      (node (ref "IC1") (pin "B17") (pinfunction "IO_31_B17") (pintype "bidirectional"))
    )
    (net (code "56") (name "IO32") (class "Default")
      (node (ref "IC1") (pin "B18") (pinfunction "IO_32_B18") (pintype "bidirectional"))
    )
    (net (code "57") (name "IO33") (class "Default")
      (node (ref "IC1") (pin "B19") (pinfunction "IO_33_B19") (pintype "bidirectional"))
      (node (ref "JP4") (pin "1") (pinfunction "1_1") (pintype "passive"))
    )
    (net (code "58") (name "IO34") (class "Default")
      (node (ref "IC1") (pin "B20") (pinfunction "IO_34_B20") (pintype "bidirectional"))
      (node (ref "JP2") (pin "1") (pinfunction "1_1") (pintype "passive"))
    )
    (net (code "59") (name "IO35") (class "Default")
      (node (ref "IC1") (pin "B21") (pinfunction "IO_35_B21") (pintype "bidirectional"))
      (node (ref "JP5") (pin "1") (pinfunction "1_1") (pintype "passive"))
    )
    (net (code "60") (name "IO36") (class "Default")
      (node (ref "IC1") (pin "B22") (pinfunction "IO_36_B22") (pintype "bidirectional"))
      (node (ref "JP6") (pin "1") (pinfunction "1_1") (pintype "passive"))
    )
    (net (code "61") (name "IO37") (class "Default")
      (node (ref "IC1") (pin "C1") (pinfunction "IO_37_C1") (pintype "bidirectional"))
      (node (ref "JP8") (pin "1") (pinfunction "1_1") (pintype "passive"))
    )
    (net (code "62") (name "IO38") (class "Default")
      (node (ref "IC1") (pin "C2") (pinfunction "IO_38_C2") (pintype "bidirectional"))
      (node (ref "JP7") (pin "1") (pinfunction "1_1") (pintype "passive"))
    )
    (net (code "63") (name "IO39") (class "Default")
      (node (ref "IC1") (pin "C3") (pinfunction "IO_39_C3") (pintype "bidirectional"))
      (node (ref "JP9") (pin "1") (pinfunction "1_1") (pintype "passive"))
    )
    (net (code "64") (name "IO40") (class "Default")
      (node (ref "IC1") (pin "C4") (pinfunction "IO_40_C4") (pintype "bidirectional"))
      (node (ref "JP10") (pin "1") (pinfunction "1_1") (pintype "passive"))
    )
    (net (code "65") (name "IO41") (class "Default")
      (node (ref "IC1") (pin "C6") (pinfunction "IO_41_C6") (pintype "bidirectional"))
      (node (ref "JP12") (pin "1") (pinfunction "1_1") (pintype "passive"))
    )
    (net (code "66") (name "IO42") (class "Default")
      (node (ref "IC1") (pin "C7") (pinfunction "IO_42_C7") (pintype "bidirectional"))
      (node (ref "JP11") (pin "1") (pinfunction "1_1") (pintype "passive"))
    )
    (net (code "67") (name "IO43") (class "Default")
      (node (ref "IC1") (pin "C8") (pinfunction "IO_43_C8") (pintype "bidirectional"))
      (node (ref "JP14") (pin "1") (pinfunction "1_1") (pintype "passive"))
    )
    (net (code "68") (name "IO44") (class "Default")
      (node (ref "IC1") (pin "C10") (pinfunction "IO_44_C10") (pintype "bidirectional"))
      (node (ref "JP15") (pin "1") (pinfunction "1_1") (pintype "passive"))
    )
    (net (code "69") (name "IO45") (class "Default")
      (node (ref "IC1") (pin "C13") (pinfunction "IO_45_C13") (pintype "bidirectional"))
      (node (ref "JP32") (pin "1") (pinfunction "1_1") (pintype "passive"))
    )
    (net (code "70") (name "IO46") (class "Default")
      (node (ref "IC1") (pin "C15") (pinfunction "IO_46_C15") (pintype "bidirectional"))
      (node (ref "JP34") (pin "1") (pinfunction "1_1") (pintype "passive"))
    )
    (net (code "71") (name "IO47") (class "Default")
      (node (ref "IC1") (pin "C17") (pinfunction "IO_47_C17") (pintype "bidirectional"))
      (node (ref "JP33") (pin "1") (pinfunction "1_1") (pintype "passive"))
    )
    (net (code "72") (name "IO48") (class "Default")
      (node (ref "IC1") (pin "C19") (pinfunction "IO_48_C19") (pintype "bidirectional"))
      (node (ref "JP35") (pin "1") (pinfunction "1_1") (pintype "passive"))
    )
    (net (code "73") (name "IO49") (class "Default")
      (node (ref "IC1") (pin "C20") (pinfunction "IO_49_C20") (pintype "bidirectional"))
      (node (ref "JP36") (pin "1") (pinfunction "1_1") (pintype "passive"))
    )
    (net (code "74") (name "IO50") (class "Default")
      (node (ref "IC1") (pin "C21") (pinfunction "IO_50_C21") (pintype "bidirectional"))
      (node (ref "JP38") (pin "1") (pinfunction "1_1") (pintype "passive"))
    )
    (net (code "75") (name "IO51") (class "Default")
      (node (ref "IC1") (pin "C22") (pinfunction "IO_51_C22") (pintype "bidirectional"))
      (node (ref "JP37") (pin "1") (pinfunction "1_1") (pintype "passive"))
    )
    (net (code "76") (name "IO53") (class "Default")
      (node (ref "IC1") (pin "D2") (pinfunction "IO_53_D2") (pintype "bidirectional"))
      (node (ref "JP40") (pin "1") (pinfunction "1_1") (pintype "passive"))
    )
    (net (code "77") (name "IO54") (class "Default")
      (node (ref "IC1") (pin "D6") (pinfunction "IO_54_D6") (pintype "bidirectional"))
      (node (ref "JP42") (pin "1") (pinfunction "1_1") (pintype "passive"))
    )
    (net (code "78") (name "IO55") (class "Default")
      (node (ref "IC1") (pin "D7") (pinfunction "IO_55_D7") (pintype "bidirectional"))
      (node (ref "JP41") (pin "1") (pinfunction "1_1") (pintype "passive"))
    )
    (net (code "79") (name "IO56") (class "Default")
      (node (ref "IC1") (pin "D10") (pinfunction "IO_56_D10") (pintype "bidirectional"))
      (node (ref "JP43") (pin "1") (pinfunction "1_1") (pintype "passive"))
    )
    (net (code "80") (name "IO57") (class "Default")
      (node (ref "IC1") (pin "D13") (pinfunction "IO_57_D13") (pintype "bidirectional"))
      (node (ref "JP44") (pin "1") (pinfunction "1_1") (pintype "passive"))
    )
    (net (code "81") (name "IO58") (class "Default")
      (node (ref "IC1") (pin "D15") (pinfunction "IO_58_D15") (pintype "bidirectional"))
      (node (ref "JP48") (pin "1") (pinfunction "1_1") (pintype "passive"))
    )
    (net (code "82") (name "IO59") (class "Default")
      (node (ref "IC1") (pin "D17") (pinfunction "IO_59_D17") (pintype "bidirectional"))
      (node (ref "JP47") (pin "1") (pinfunction "1_1") (pintype "passive"))
    )
    (net (code "83") (name "IO60") (class "Default")
      (node (ref "IC1") (pin "D19") (pinfunction "IO_60_D19") (pintype "bidirectional"))
      (node (ref "JP49") (pin "1") (pinfunction "1_1") (pintype "passive"))
    )
    (net (code "84") (name "IO61") (class "Default")
      (node (ref "IC1") (pin "D20") (pinfunction "IO_61_D20") (pintype "bidirectional"))
      (node (ref "JP50") (pin "1") (pinfunction "1_1") (pintype "passive"))
    )
    (net (code "85") (name "IO62") (class "Default")
      (node (ref "IC1") (pin "D21") (pinfunction "IO_62_D21") (pintype "bidirectional"))
      (node (ref "JP52") (pin "1") (pinfunction "1_1") (pintype "passive"))
    )
    (net (code "86") (name "IO63") (class "Default")
      (node (ref "IC1") (pin "D22") (pinfunction "IO_63_D22") (pintype "bidirectional"))
      (node (ref "JP51") (pin "1") (pinfunction "1_1") (pintype "passive"))
    )
    (net (code "87") (name "IO64") (class "Default")
      (node (ref "IC1") (pin "E1") (pinfunction "IO_64_E1") (pintype "bidirectional"))
      (node (ref "JP53") (pin "1") (pinfunction "1_1") (pintype "passive"))
    )
    (net (code "88") (name "IO66") (class "Default")
      (node (ref "IC1") (pin "E3") (pinfunction "IO_66_E3") (pintype "bidirectional"))
      (node (ref "JP56") (pin "1") (pinfunction "1_1") (pintype "passive"))
    )
    (net (code "89") (name "IO67") (class "Default")
      (node (ref "IC1") (pin "E4") (pinfunction "IO_67_E4") (pintype "bidirectional"))
      (node (ref "JP55") (pin "1") (pinfunction "1_1") (pintype "passive"))
    )
    (net (code "90") (name "IO68") (class "Default")
      (node (ref "IC1") (pin "E5") (pinfunction "IO_68_E5") (pintype "bidirectional"))
      (node (ref "JP58") (pin "1") (pinfunction "1_1") (pintype "passive"))
    )
    (net (code "91") (name "IO69") (class "Default")
      (node (ref "IC1") (pin "E6") (pinfunction "IO_69_E6") (pintype "bidirectional"))
      (node (ref "JP59") (pin "1") (pinfunction "1_1") (pintype "passive"))
    )
    (net (code "92") (name "IO70") (class "Default")
      (node (ref "IC1") (pin "E7") (pinfunction "IO_70_E7") (pintype "bidirectional"))
      (node (ref "JP60") (pin "1") (pinfunction "1_1") (pintype "passive"))
    )
    (net (code "93") (name "IO71") (class "Default")
      (node (ref "IC1") (pin "E9") (pinfunction "IO_71_E9") (pintype "bidirectional"))
      (node (ref "JP62") (pin "1") (pinfunction "1_1") (pintype "passive"))
    )
    (net (code "94") (name "IO72") (class "Default")
      (node (ref "IC1") (pin "E10") (pinfunction "IO_72_E10") (pintype "bidirectional"))
      (node (ref "JP61") (pin "1") (pinfunction "1_1") (pintype "passive"))
    )
    (net (code "95") (name "IO73") (class "Default")
      (node (ref "IC1") (pin "E11") (pinfunction "IO_73_E11") (pintype "bidirectional"))
      (node (ref "JP63") (pin "1") (pinfunction "1_1") (pintype "passive"))
    )
    (net (code "96") (name "IO74") (class "Default")
      (node (ref "IC1") (pin "E12") (pinfunction "IO_74_E12") (pintype "bidirectional"))
      (node (ref "JP64") (pin "1") (pinfunction "1_1") (pintype "passive"))
    )
    (net (code "97") (name "IO75") (class "Default")
      (node (ref "IC1") (pin "E13") (pinfunction "IO_75_E13") (pintype "bidirectional"))
      (node (ref "JP66") (pin "1") (pinfunction "1_1") (pintype "passive"))
    )
    (net (code "98") (name "IO76") (class "Default")
      (node (ref "IC1") (pin "E14") (pinfunction "IO_76_E14") (pintype "bidirectional"))
      (node (ref "JP65") (pin "1") (pinfunction "1_1") (pintype "passive"))
    )
    (net (code "99") (name "IO77") (class "Default")
      (node (ref "IC1") (pin "E15") (pinfunction "IO_77_E15") (pintype "bidirectional"))
      (node (ref "JP67") (pin "1") (pinfunction "1_1") (pintype "passive"))
    )
    (net (code "100") (name "IO78") (class "Default")
      (node (ref "IC1") (pin "E16") (pinfunction "IO_78_E16") (pintype "bidirectional"))
      (node (ref "JP68") (pin "1") (pinfunction "1_1") (pintype "passive"))
    )
    (net (code "101") (name "IO79") (class "Default")
      (node (ref "IC1") (pin "E21") (pinfunction "IO_79_E21") (pintype "bidirectional"))
      (node (ref "JP70") (pin "1") (pinfunction "1_1") (pintype "passive"))
    )
    (net (code "102") (name "IO80") (class "Default")
      (node (ref "IC1") (pin "E22") (pinfunction "IO_80_E22") (pintype "bidirectional"))
      (node (ref "JP69") (pin "1") (pinfunction "1_1") (pintype "passive"))
    )
    (net (code "103") (name "IO81") (class "Default")
      (node (ref "IC1") (pin "F1") (pinfunction "IO_81_F1") (pintype "bidirectional"))
      (node (ref "JP71") (pin "1") (pinfunction "1_1") (pintype "passive"))
    )
    (net (code "104") (name "IO82") (class "Default")
      (node (ref "IC1") (pin "F2") (pinfunction "IO_82_F2") (pintype "bidirectional"))
      (node (ref "JP72") (pin "1") (pinfunction "1_1") (pintype "passive"))
    )
    (net (code "105") (name "IO83") (class "Default")
      (node (ref "IC1") (pin "F7") (pinfunction "IO_83_F7") (pintype "bidirectional"))
    )
    (net (code "106") (name "IO84") (class "Default")
      (node (ref "IC1") (pin "F8") (pinfunction "IO_84_F8") (pintype "bidirectional"))
    )
    (net (code "107") (name "IO85") (class "Default")
      (node (ref "IC1") (pin "F9") (pinfunction "IO_85_F9") (pintype "bidirectional"))
    )
    (net (code "108") (name "IO86") (class "Default")
      (node (ref "IC1") (pin "F10") (pinfunction "IO_86_F10") (pintype "bidirectional"))
    )
    (net (code "109") (name "IO87") (class "Default")
      (node (ref "IC1") (pin "F11") (pinfunction "IO_87_F11") (pintype "bidirectional"))
    )
    (net (code "110") (name "IO88") (class "Default")
      (node (ref "IC1") (pin "F13") (pinfunction "IO_88_F13") (pintype "bidirectional"))
    )
    (net (code "111") (name "IO89") (class "Default")
      (node (ref "IC1") (pin "F14") (pinfunction "IO_89_F14") (pintype "bidirectional"))
    )
    (net (code "112") (name "IO90") (class "Default")
      (node (ref "IC1") (pin "F15") (pinfunction "IO_90_F15") (pintype "bidirectional"))
    )
    (net (code "113") (name "IO91") (class "Default")
      (node (ref "IC1") (pin "F16") (pinfunction "IO_91_F16") (pintype "bidirectional"))
    )
    (net (code "114") (name "IO92") (class "Default")
      (node (ref "IC1") (pin "F17") (pinfunction "IO_92_F17") (pintype "bidirectional"))
    )
    (net (code "115") (name "IO93") (class "Default")
      (node (ref "IC1") (pin "F19") (pinfunction "IO_93_F19") (pintype "bidirectional"))
    )
    (net (code "116") (name "IO94") (class "Default")
      (node (ref "IC1") (pin "F20") (pinfunction "IO_94_F20") (pintype "bidirectional"))
    )
    (net (code "117") (name "IO95") (class "Default")
      (node (ref "IC1") (pin "F21") (pinfunction "IO_95_F21") (pintype "bidirectional"))
    )
    (net (code "118") (name "IO96") (class "Default")
      (node (ref "IC1") (pin "F22") (pinfunction "IO_96_F22") (pintype "bidirectional"))
    )
    (net (code "119") (name "IO97") (class "Default")
      (node (ref "IC1") (pin "G3") (pinfunction "IO_97_G3") (pintype "bidirectional"))
    )
    (net (code "120") (name "IO98") (class "Default")
      (node (ref "IC1") (pin "G4") (pinfunction "IO_98_G4") (pintype "bidirectional"))
    )
    (net (code "121") (name "IO99") (class "Default")
      (node (ref "IC1") (pin "G5") (pinfunction "IO_99_G5") (pintype "bidirectional"))
    )
    (net (code "122") (name "IO100") (class "Default")
      (node (ref "IC1") (pin "G7") (pinfunction "IO_100_G7") (pintype "bidirectional"))
    )
    (net (code "123") (name "IO101") (class "Default")
      (node (ref "IC1") (pin "G8") (pinfunction "IO_101_G8") (pintype "bidirectional"))
    )
    (net (code "124") (name "IO102") (class "Default")
      (node (ref "IC1") (pin "G9") (pinfunction "IO_102_G9") (pintype "bidirectional"))
    )
    (net (code "125") (name "IO103") (class "Default")
      (node (ref "IC1") (pin "G10") (pinfunction "IO_103_G10") (pintype "bidirectional"))
    )
    (net (code "126") (name "IO104") (class "Default")
      (node (ref "IC1") (pin "G11") (pinfunction "IO_104_G11") (pintype "bidirectional"))
    )
    (net (code "127") (name "IO105") (class "Default")
      (node (ref "IC1") (pin "G13") (pinfunction "IO_105_G13") (pintype "bidirectional"))
    )
    (net (code "128") (name "IO106") (class "Default")
      (node (ref "IC1") (pin "G14") (pinfunction "IO_106_G14") (pintype "bidirectional"))
    )
    (net (code "129") (name "IO107") (class "Default")
      (node (ref "IC1") (pin "G15") (pinfunction "IO_107_G15") (pintype "bidirectional"))
    )
    (net (code "130") (name "IO108") (class "Default")
      (node (ref "IC1") (pin "G16") (pinfunction "IO_108_G16") (pintype "bidirectional"))
    )
    (net (code "131") (name "IO109") (class "Default")
      (node (ref "IC1") (pin "G17") (pinfunction "IO_109_G17") (pintype "bidirectional"))
    )
    (net (code "132") (name "IO110") (class "Default")
      (node (ref "IC1") (pin "G18") (pinfunction "IO_110_G18") (pintype "bidirectional"))
    )
    (net (code "133") (name "IO111") (class "Default")
      (node (ref "IC1") (pin "H1") (pinfunction "IO_111_H1") (pintype "bidirectional"))
    )
    (net (code "134") (name "IO112") (class "Default")
      (node (ref "IC1") (pin "H2") (pinfunction "IO_112_H2") (pintype "bidirectional"))
    )
    (net (code "135") (name "IO113") (class "Default")
      (node (ref "IC1") (pin "H5") (pinfunction "IO_113_H5") (pintype "bidirectional"))
    )
    (net (code "136") (name "IO114") (class "Default")
      (node (ref "IC1") (pin "H6") (pinfunction "IO_114_H6") (pintype "bidirectional"))
    )
    (net (code "137") (name "IO115") (class "Default")
      (node (ref "IC1") (pin "H7") (pinfunction "IO_115_H7") (pintype "bidirectional"))
    )
    (net (code "138") (name "IO116") (class "Default")
      (node (ref "IC1") (pin "H8") (pinfunction "IO_116_H8") (pintype "bidirectional"))
    )
    (net (code "139") (name "IO117") (class "Default")
      (node (ref "IC1") (pin "H10") (pinfunction "IO_117_H10") (pintype "bidirectional"))
    )
    (net (code "140") (name "IO118") (class "Default")
      (node (ref "IC1") (pin "H11") (pinfunction "IO_118_H11") (pintype "bidirectional"))
    )
    (net (code "141") (name "IO119") (class "Default")
      (node (ref "IC1") (pin "H14") (pinfunction "IO_119_H14") (pintype "bidirectional"))
    )
    (net (code "142") (name "IO120") (class "Default")
      (node (ref "IC1") (pin "H15") (pinfunction "IO_120_H15") (pintype "bidirectional"))
    )
    (net (code "143") (name "IO121") (class "Default")
      (node (ref "IC1") (pin "H16") (pinfunction "IO_121_H16") (pintype "bidirectional"))
    )
    (net (code "144") (name "IO122") (class "Default")
      (node (ref "IC1") (pin "H17") (pinfunction "IO_122_H17") (pintype "bidirectional"))
    )
    (net (code "145") (name "IO123") (class "Default")
      (node (ref "IC1") (pin "H18") (pinfunction "IO_123_H18") (pintype "bidirectional"))
    )
    (net (code "146") (name "IO124") (class "Default")
      (node (ref "IC1") (pin "H19") (pinfunction "IO_124_H19") (pintype "bidirectional"))
    )
    (net (code "147") (name "IO125") (class "Default")
      (node (ref "IC1") (pin "H20") (pinfunction "IO_125_H20") (pintype "bidirectional"))
    )
    (net (code "148") (name "IO126") (class "Default")
      (node (ref "IC1") (pin "H21") (pinfunction "IO_126_H21") (pintype "bidirectional"))
    )
    (net (code "149") (name "IO127") (class "Default")
      (node (ref "IC1") (pin "H22") (pinfunction "IO_127_H22") (pintype "bidirectional"))
    )
    (net (code "150") (name "IO128") (class "Default")
      (node (ref "IC1") (pin "J1") (pinfunction "IO_128_J1") (pintype "bidirectional"))
    )
    (net (code "151") (name "IO129") (class "Default")
      (node (ref "IC1") (pin "J2") (pinfunction "IO_129_J2") (pintype "bidirectional"))
    )
    (net (code "152") (name "IO130") (class "Default")
      (node (ref "IC1") (pin "J3") (pinfunction "IO_130_J3") (pintype "bidirectional"))
    )
    (net (code "153") (name "IO131") (class "Default")
      (node (ref "IC1") (pin "J4") (pinfunction "IO_131_J4") (pintype "bidirectional"))
    )
    (net (code "154") (name "IO132") (class "Default")
      (node (ref "IC1") (pin "J5") (pinfunction "IO_132_J5") (pintype "bidirectional"))
    )
    (net (code "155") (name "IO133") (class "Default")
      (node (ref "IC1") (pin "J6") (pinfunction "IO_133_J6") (pintype "bidirectional"))
    )
    (net (code "156") (name "IO134") (class "Default")
      (node (ref "IC1") (pin "J7") (pinfunction "IO_134_J7") (pintype "bidirectional"))
    )
    (net (code "157") (name "IO135") (class "Default")
      (node (ref "IC1") (pin "J8") (pinfunction "IO_135_J8") (pintype "bidirectional"))
    )
    (net (code "158") (name "IO136") (class "Default")
      (node (ref "IC1") (pin "J17") (pinfunction "IO_136_J17") (pintype "bidirectional"))
    )
    (net (code "159") (name "IO137") (class "Default")
      (node (ref "IC1") (pin "J18") (pinfunction "IO_137_J18") (pintype "bidirectional"))
    )
    (net (code "160") (name "IO138") (class "Default")
      (node (ref "IC1") (pin "J21") (pinfunction "IO_138_J21") (pintype "bidirectional"))
    )
    (net (code "161") (name "IO139") (class "Default")
      (node (ref "IC1") (pin "J22") (pinfunction "IO_139_J22") (pintype "bidirectional"))
    )
    (net (code "162") (name "IO141") (class "Default")
      (node (ref "IC1") (pin "K7") (pinfunction "IO_141_K7") (pintype "bidirectional"))
    )
    (net (code "163") (name "IO142") (class "Default")
      (node (ref "IC1") (pin "K8") (pinfunction "IO_142_K8") (pintype "bidirectional"))
    )
    (net (code "164") (name "IO143") (class "Default")
      (node (ref "IC1") (pin "K17") (pinfunction "IO_143_K17") (pintype "bidirectional"))
    )
    (net (code "165") (name "IO144") (class "Default")
      (node (ref "IC1") (pin "K18") (pinfunction "IO_144_K18") (pintype "bidirectional"))
    )
    (net (code "166") (name "IO145") (class "Default")
      (node (ref "IC1") (pin "K19") (pinfunction "IO_145_K19") (pintype "bidirectional"))
    )
    (net (code "167") (name "IO146") (class "Default")
      (node (ref "IC1") (pin "K21") (pinfunction "IO_146_K21") (pintype "bidirectional"))
    )
    (net (code "168") (name "IO147") (class "Default")
      (node (ref "IC1") (pin "K22") (pinfunction "IO_147_K22") (pintype "bidirectional"))
    )
    (net (code "169") (name "IO148") (class "Default")
      (node (ref "IC1") (pin "L6") (pinfunction "IO_148_L6") (pintype "bidirectional"))
    )
    (net (code "170") (name "IO149") (class "Default")
      (node (ref "IC1") (pin "L7") (pinfunction "IO_149_L7") (pintype "bidirectional"))
    )
    (net (code "171") (name "IO150") (class "Default")
      (node (ref "IC1") (pin "L8") (pinfunction "IO_150_L8") (pintype "bidirectional"))
    )
    (net (code "172") (name "IO151") (class "Default")
      (node (ref "IC1") (pin "L21") (pinfunction "IO_151_L21") (pintype "bidirectional"))
    )
    (net (code "173") (name "IO152") (class "Default")
      (node (ref "IC1") (pin "L22") (pinfunction "IO_152_L22") (pintype "bidirectional"))
    )
    (net (code "174") (name "IO153") (class "Default")
      (node (ref "IC1") (pin "M1") (pinfunction "IO_153_M1") (pintype "bidirectional"))
    )
    (net (code "175") (name "IO154") (class "Default")
      (node (ref "IC1") (pin "M2") (pinfunction "IO_154_M2") (pintype "bidirectional"))
    )
    (net (code "176") (name "IO155") (class "Default")
      (node (ref "IC1") (pin "M3") (pinfunction "IO_155_M3") (pintype "bidirectional"))
    )
    (net (code "177") (name "IO156") (class "Default")
      (node (ref "IC1") (pin "M4") (pinfunction "IO_156_M4") (pintype "bidirectional"))
    )
    (net (code "178") (name "IO157") (class "Default")
      (node (ref "IC1") (pin "M5") (pinfunction "IO_157_M5") (pintype "bidirectional"))
    )
    (net (code "179") (name "IO158") (class "Default")
      (node (ref "IC1") (pin "M6") (pinfunction "IO_158_M6") (pintype "bidirectional"))
    )
    (net (code "180") (name "IO159") (class "Default")
      (node (ref "IC1") (pin "M7") (pinfunction "IO_159_M7") (pintype "bidirectional"))
    )
    (net (code "181") (name "IO160") (class "Default")
      (node (ref "IC1") (pin "M8") (pinfunction "IO_160_M8") (pintype "bidirectional"))
    )
    (net (code "182") (name "IO161") (class "Default")
      (node (ref "IC1") (pin "M16") (pinfunction "IO_161_M16") (pintype "bidirectional"))
    )
    (net (code "183") (name "IO162") (class "Default")
      (node (ref "IC1") (pin "M19") (pinfunction "IO_162_M19") (pintype "bidirectional"))
    )
    (net (code "184") (name "IO163") (class "Default")
      (node (ref "IC1") (pin "M20") (pinfunction "IO_163_M20") (pintype "bidirectional"))
    )
    (net (code "185") (name "IO164") (class "Default")
      (node (ref "IC1") (pin "M21") (pinfunction "IO_164_M21") (pintype "bidirectional"))
    )
    (net (code "186") (name "IO165") (class "Default")
      (node (ref "IC1") (pin "M22") (pinfunction "IO_165_M22") (pintype "bidirectional"))
    )
    (net (code "187") (name "IO166") (class "Default")
      (node (ref "IC1") (pin "N1") (pinfunction "IO_166_N1") (pintype "bidirectional"))
    )
    (net (code "188") (name "IO167") (class "Default")
      (node (ref "IC1") (pin "N2") (pinfunction "IO_167_N2") (pintype "bidirectional"))
    )
    (net (code "189") (name "IO168") (class "Default")
      (node (ref "IC1") (pin "N5") (pinfunction "IO_168_N5") (pintype "bidirectional"))
    )
    (net (code "190") (name "IO169") (class "Default")
      (node (ref "IC1") (pin "N6") (pinfunction "IO_169_N6") (pintype "bidirectional"))
    )
    (net (code "191") (name "IO170") (class "Default")
      (node (ref "IC1") (pin "N7") (pinfunction "IO_170_N7") (pintype "bidirectional"))
    )
    (net (code "192") (name "IO171") (class "Default")
      (node (ref "IC1") (pin "N8") (pinfunction "IO_171_N8") (pintype "bidirectional"))
    )
    (net (code "193") (name "IO172") (class "Default")
      (node (ref "IC1") (pin "N16") (pinfunction "IO_172_N16") (pintype "bidirectional"))
    )
    (net (code "194") (name "IO173") (class "Default")
      (node (ref "IC1") (pin "N17") (pinfunction "IO_173_N17") (pintype "bidirectional"))
    )
    (net (code "195") (name "IO174") (class "Default")
      (node (ref "IC1") (pin "N18") (pinfunction "IO_174_N18") (pintype "bidirectional"))
    )
    (net (code "196") (name "IO175") (class "Default")
      (node (ref "IC1") (pin "N19") (pinfunction "IO_175_N19") (pintype "bidirectional"))
    )
    (net (code "197") (name "IO176") (class "Default")
      (node (ref "IC1") (pin "N20") (pinfunction "IO_176_N20") (pintype "bidirectional"))
    )
    (net (code "198") (name "IO177") (class "Default")
      (node (ref "IC1") (pin "N21") (pinfunction "IO_177_N21") (pintype "bidirectional"))
    )
    (net (code "199") (name "IO178") (class "Default")
      (node (ref "IC1") (pin "N22") (pinfunction "IO_178_N22") (pintype "bidirectional"))
    )
    (net (code "200") (name "IO179") (class "Default")
      (node (ref "IC1") (pin "P1") (pinfunction "IO_179_P1") (pintype "bidirectional"))
    )
    (net (code "201") (name "IO180") (class "Default")
      (node (ref "IC1") (pin "P2") (pinfunction "IO_180_P2") (pintype "bidirectional"))
    )
    (net (code "202") (name "IO181") (class "Default")
      (node (ref "IC1") (pin "P3") (pinfunction "IO_181_P3") (pintype "bidirectional"))
    )
    (net (code "203") (name "IO182") (class "Default")
      (node (ref "IC1") (pin "P4") (pinfunction "IO_182_P4") (pintype "bidirectional"))
    )
    (net (code "204") (name "IO183") (class "Default")
      (node (ref "IC1") (pin "P5") (pinfunction "IO_183_P5") (pintype "bidirectional"))
    )
    (net (code "205") (name "IO184") (class "Default")
      (node (ref "IC1") (pin "P6") (pinfunction "IO_184_P6") (pintype "bidirectional"))
    )
    (net (code "206") (name "IO185") (class "Default")
      (node (ref "IC1") (pin "P7") (pinfunction "IO_185_P7") (pintype "bidirectional"))
    )
    (net (code "207") (name "IO186") (class "Default")
      (node (ref "IC1") (pin "P15") (pinfunction "IO_186_P15") (pintype "bidirectional"))
    )
    (net (code "208") (name "IO187") (class "Default")
      (node (ref "IC1") (pin "P16") (pinfunction "IO_187_P16") (pintype "bidirectional"))
    )
    (net (code "209") (name "IO188") (class "Default")
      (node (ref "IC1") (pin "P17") (pinfunction "IO_188_P17") (pintype "bidirectional"))
    )
    (net (code "210") (name "IO189") (class "Default")
      (node (ref "IC1") (pin "P20") (pinfunction "IO_189_P20") (pintype "bidirectional"))
    )
    (net (code "211") (name "IO190") (class "Default")
      (node (ref "IC1") (pin "P21") (pinfunction "IO_190_P21") (pintype "bidirectional"))
    )
    (net (code "212") (name "IO191") (class "Default")
      (node (ref "IC1") (pin "P22") (pinfunction "IO_191_P22") (pintype "bidirectional"))
    )
    (net (code "213") (name "IO192") (class "Default")
      (node (ref "IC1") (pin "R1") (pinfunction "IO_192_R1") (pintype "bidirectional"))
    )
    (net (code "214") (name "IO193") (class "Default")
      (node (ref "IC1") (pin "R2") (pinfunction "IO_193_R2") (pintype "bidirectional"))
    )
    (net (code "215") (name "IO194") (class "Default")
      (node (ref "IC1") (pin "R5") (pinfunction "IO_194_R5") (pintype "bidirectional"))
    )
    (net (code "216") (name "IO195") (class "Default")
      (node (ref "IC1") (pin "R6") (pinfunction "IO_195_R6") (pintype "bidirectional"))
    )
    (net (code "217") (name "IO196") (class "Default")
      (node (ref "IC1") (pin "R7") (pinfunction "IO_196_R7") (pintype "bidirectional"))
    )
    (net (code "218") (name "IO197") (class "Default")
      (node (ref "IC1") (pin "R14") (pinfunction "IO_197_R14") (pintype "bidirectional"))
    )
    (net (code "219") (name "IO198") (class "Default")
      (node (ref "IC1") (pin "R15") (pinfunction "IO_198_R15") (pintype "bidirectional"))
    )
    (net (code "220") (name "IO199") (class "Default")
      (node (ref "IC1") (pin "R16") (pinfunction "IO_199_R16") (pintype "bidirectional"))
    )
    (net (code "221") (name "IO200") (class "Default")
      (node (ref "IC1") (pin "R17") (pinfunction "IO_200_R17") (pintype "bidirectional"))
    )
    (net (code "222") (name "IO201") (class "Default")
      (node (ref "IC1") (pin "R18") (pinfunction "IO_201_R18") (pintype "bidirectional"))
    )
    (net (code "223") (name "IO202") (class "Default")
      (node (ref "IC1") (pin "R19") (pinfunction "IO_202_R19") (pintype "bidirectional"))
    )
    (net (code "224") (name "IO203") (class "Default")
      (node (ref "IC1") (pin "R20") (pinfunction "IO_203_R20") (pintype "bidirectional"))
    )
    (net (code "225") (name "IO204") (class "Default")
      (node (ref "IC1") (pin "R21") (pinfunction "IO_204_R21") (pintype "bidirectional"))
    )
    (net (code "226") (name "IO205") (class "Default")
      (node (ref "IC1") (pin "R22") (pinfunction "IO_205_R22") (pintype "bidirectional"))
    )
    (net (code "227") (name "IO206") (class "Default")
      (node (ref "IC1") (pin "T3") (pinfunction "IO_206_T3") (pintype "bidirectional"))
    )
    (net (code "228") (name "IO207") (class "Default")
      (node (ref "IC1") (pin "T4") (pinfunction "IO_207_T4") (pintype "bidirectional"))
    )
    (net (code "229") (name "IO208") (class "Default")
      (node (ref "IC1") (pin "T5") (pinfunction "IO_208_T5") (pintype "bidirectional"))
    )
    (net (code "230") (name "IO209") (class "Default")
      (node (ref "IC1") (pin "T7") (pinfunction "IO_209_T7") (pintype "bidirectional"))
    )
    (net (code "231") (name "IO210") (class "Default")
      (node (ref "IC1") (pin "T8") (pinfunction "IO_210_T8") (pintype "bidirectional"))
    )
    (net (code "232") (name "IO211") (class "Default")
      (node (ref "IC1") (pin "T9") (pinfunction "IO_211_T9") (pintype "bidirectional"))
    )
    (net (code "233") (name "IO212") (class "Default")
      (node (ref "IC1") (pin "T10") (pinfunction "IO_212_T10") (pintype "bidirectional"))
    )
    (net (code "234") (name "IO213") (class "Default")
      (node (ref "IC1") (pin "T11") (pinfunction "IO_213_T11") (pintype "bidirectional"))
    )
    (net (code "235") (name "IO214") (class "Default")
      (node (ref "IC1") (pin "T12") (pinfunction "IO_214_T12") (pintype "bidirectional"))
    )
    (net (code "236") (name "IO215") (class "Default")
      (node (ref "IC1") (pin "T13") (pinfunction "IO_215_T13") (pintype "bidirectional"))
    )
    (net (code "237") (name "IO216") (class "Default")
      (node (ref "IC1") (pin "T14") (pinfunction "IO_216_T14") (pintype "bidirectional"))
    )
    (net (code "238") (name "IO217") (class "Default")
      (node (ref "IC1") (pin "T15") (pinfunction "IO_217_T15") (pintype "bidirectional"))
    )
    (net (code "239") (name "IO218") (class "Default")
      (node (ref "IC1") (pin "T16") (pinfunction "IO_218_T16") (pintype "bidirectional"))
    )
    (net (code "240") (name "IO219") (class "Default")
      (node (ref "IC1") (pin "T17") (pinfunction "IO_219_T17") (pintype "bidirectional"))
    )
    (net (code "241") (name "IO220") (class "Default")
      (node (ref "IC1") (pin "T18") (pinfunction "IO_220_T18") (pintype "bidirectional"))
    )
    (net (code "242") (name "IO221") (class "Default")
      (node (ref "IC1") (pin "U1") (pinfunction "IO_221_U1") (pintype "bidirectional"))
    )
    (net (code "243") (name "IO222") (class "Default")
      (node (ref "IC1") (pin "U2") (pinfunction "IO_222_U2") (pintype "bidirectional"))
    )
    (net (code "244") (name "IO223") (class "Default")
      (node (ref "IC1") (pin "U7") (pinfunction "IO_223_U7") (pintype "bidirectional"))
    )
    (net (code "245") (name "IO224") (class "Default")
      (node (ref "IC1") (pin "U8") (pinfunction "IO_224_U8") (pintype "bidirectional"))
    )
    (net (code "246") (name "IO225") (class "Default")
      (node (ref "IC1") (pin "U9") (pinfunction "IO_225_U9") (pintype "bidirectional"))
    )
    (net (code "247") (name "IO226") (class "Default")
      (node (ref "IC1") (pin "U10") (pinfunction "IO_226_U10") (pintype "bidirectional"))
    )
    (net (code "248") (name "IO227") (class "Default")
      (node (ref "IC1") (pin "U11") (pinfunction "IO_227_U11") (pintype "bidirectional"))
    )
    (net (code "249") (name "IO228") (class "Default")
      (node (ref "IC1") (pin "U12") (pinfunction "IO_228_U12") (pintype "bidirectional"))
    )
    (net (code "250") (name "IO229") (class "Default")
      (node (ref "IC1") (pin "U13") (pinfunction "IO_229_U13") (pintype "bidirectional"))
    )
    (net (code "251") (name "IO230") (class "Default")
      (node (ref "IC1") (pin "U14") (pinfunction "IO_230_U14") (pintype "bidirectional"))
    )
    (net (code "252") (name "IO231") (class "Default")
      (node (ref "IC1") (pin "U15") (pinfunction "IO_231_U15") (pintype "bidirectional"))
    )
    (net (code "253") (name "IO232") (class "Default")
      (node (ref "IC1") (pin "U16") (pinfunction "IO_232_U16") (pintype "bidirectional"))
    )
    (net (code "254") (name "IO233") (class "Default")
      (node (ref "IC1") (pin "U17") (pinfunction "IO_233_U17") (pintype "bidirectional"))
    )
    (net (code "255") (name "IO234") (class "Default")
      (node (ref "IC1") (pin "U19") (pinfunction "IO_234_U19") (pintype "bidirectional"))
    )
    (net (code "256") (name "IO235") (class "Default")
      (node (ref "IC1") (pin "U20") (pinfunction "IO_235_U20") (pintype "bidirectional"))
    )
    (net (code "257") (name "IO236") (class "Default")
      (node (ref "IC1") (pin "U21") (pinfunction "IO_236_U21") (pintype "bidirectional"))
    )
    (net (code "258") (name "IO237") (class "Default")
      (node (ref "IC1") (pin "U22") (pinfunction "IO_237_U22") (pintype "bidirectional"))
    )
    (net (code "259") (name "IO238") (class "Default")
      (node (ref "IC1") (pin "V1") (pinfunction "IO_238_V1") (pintype "bidirectional"))
    )
    (net (code "260") (name "IO239") (class "Default")
      (node (ref "IC1") (pin "V2") (pinfunction "IO_239_V2") (pintype "bidirectional"))
    )
    (net (code "261") (name "IO240") (class "Default")
      (node (ref "IC1") (pin "V3") (pinfunction "IO_240_V3") (pintype "bidirectional"))
    )
    (net (code "262") (name "IO241") (class "Default")
      (node (ref "IC1") (pin "V4") (pinfunction "IO_241_V4") (pintype "bidirectional"))
    )
    (net (code "263") (name "IO242") (class "Default")
      (node (ref "IC1") (pin "V5") (pinfunction "IO_242_V5") (pintype "bidirectional"))
    )
    (net (code "264") (name "IO243") (class "Default")
      (node (ref "IC1") (pin "V6") (pinfunction "IO_243_V6") (pintype "bidirectional"))
    )
    (net (code "265") (name "IO244") (class "Default")
      (node (ref "IC1") (pin "V7") (pinfunction "IO_244_V7") (pintype "bidirectional"))
    )
    (net (code "266") (name "IO245") (class "Default")
      (node (ref "IC1") (pin "V8") (pinfunction "IO_245_V8") (pintype "bidirectional"))
    )
    (net (code "267") (name "IO246") (class "Default")
      (node (ref "IC1") (pin "V9") (pinfunction "IO_246_V9") (pintype "bidirectional"))
    )
    (net (code "268") (name "IO247") (class "Default")
      (node (ref "IC1") (pin "V10") (pinfunction "IO_247_V10") (pintype "bidirectional"))
    )
    (net (code "269") (name "IO248") (class "Default")
      (node (ref "IC1") (pin "V11") (pinfunction "IO_248_V11") (pintype "bidirectional"))
    )
    (net (code "270") (name "IO249") (class "Default")
      (node (ref "IC1") (pin "V12") (pinfunction "IO_249_V12") (pintype "bidirectional"))
    )
    (net (code "271") (name "IO250") (class "Default")
      (node (ref "IC1") (pin "V13") (pinfunction "IO_250_V13") (pintype "bidirectional"))
    )
    (net (code "272") (name "IO251") (class "Default")
      (node (ref "IC1") (pin "V14") (pinfunction "IO_251_V14") (pintype "bidirectional"))
    )
    (net (code "273") (name "IO252") (class "Default")
      (node (ref "IC1") (pin "V15") (pinfunction "IO_252_V15") (pintype "bidirectional"))
    )
    (net (code "274") (name "IO253") (class "Default")
      (node (ref "IC1") (pin "V16") (pinfunction "IO_253_V16") (pintype "bidirectional"))
    )
    (net (code "275") (name "IO254") (class "Default")
      (node (ref "IC1") (pin "V21") (pinfunction "IO_254_V21") (pintype "bidirectional"))
    )
    (net (code "276") (name "IO255") (class "Default")
      (node (ref "IC1") (pin "V22") (pinfunction "IO_255_V22") (pintype "bidirectional"))
    )
    (net (code "277") (name "IO256") (class "Default")
      (node (ref "IC1") (pin "W1") (pinfunction "IO_256_W1") (pintype "bidirectional"))
    )
    (net (code "278") (name "IO257") (class "Default")
      (node (ref "IC1") (pin "W2") (pinfunction "IO_257_W2") (pintype "bidirectional"))
    )
    (net (code "279") (name "IO258") (class "Default")
      (node (ref "IC1") (pin "W6") (pinfunction "IO_258_W6") (pintype "bidirectional"))
    )
    (net (code "280") (name "IO259") (class "Default")
      (node (ref "IC1") (pin "W7") (pinfunction "IO_259_W7") (pintype "bidirectional"))
    )
    (net (code "281") (name "IO260") (class "Default")
      (node (ref "IC1") (pin "W8") (pinfunction "IO_260_W8") (pintype "bidirectional"))
    )
    (net (code "282") (name "IO261") (class "Default")
      (node (ref "IC1") (pin "W10") (pinfunction "IO_261_W10") (pintype "bidirectional"))
    )
    (net (code "283") (name "IO262") (class "Default")
      (node (ref "IC1") (pin "W13") (pinfunction "IO_262_W13") (pintype "bidirectional"))
    )
    (net (code "284") (name "IO263") (class "Default")
      (node (ref "IC1") (pin "W14") (pinfunction "IO_263_W14") (pintype "bidirectional"))
    )
    (net (code "285") (name "IO264") (class "Default")
      (node (ref "IC1") (pin "W15") (pinfunction "IO_264_W15") (pintype "bidirectional"))
    )
    (net (code "286") (name "IO265") (class "Default")
      (node (ref "IC1") (pin "W17") (pinfunction "IO_265_W17") (pintype "bidirectional"))
    )
    (net (code "287") (name "IO266") (class "Default")
      (node (ref "IC1") (pin "W19") (pinfunction "IO_266_W19") (pintype "bidirectional"))
    )
    (net (code "288") (name "IO267") (class "Default")
      (node (ref "IC1") (pin "W20") (pinfunction "IO_267_W20") (pintype "bidirectional"))
    )
    (net (code "289") (name "IO268") (class "Default")
      (node (ref "IC1") (pin "W21") (pinfunction "IO_268_W21") (pintype "bidirectional"))
    )
    (net (code "290") (name "IO269") (class "Default")
      (node (ref "IC1") (pin "W22") (pinfunction "IO_269_W22") (pintype "bidirectional"))
    )
    (net (code "291") (name "IO270") (class "Default")
      (node (ref "IC1") (pin "Y1") (pinfunction "IO_270_Y1") (pintype "bidirectional"))
    )
    (net (code "292") (name "IO271") (class "Default")
      (node (ref "IC1") (pin "Y2") (pinfunction "IO_271_Y2") (pintype "bidirectional"))
    )
    (net (code "293") (name "IO272") (class "Default")
      (node (ref "IC1") (pin "Y3") (pinfunction "IO_272_Y3") (pintype "bidirectional"))
    )
    (net (code "294") (name "IO273") (class "Default")
      (node (ref "IC1") (pin "Y4") (pinfunction "IO_273_Y4") (pintype "bidirectional"))
    )
    (net (code "295") (name "IO274") (class "Default")
      (node (ref "IC1") (pin "Y6") (pinfunction "IO_274_Y6") (pintype "bidirectional"))
    )
    (net (code "296") (name "IO275") (class "Default")
      (node (ref "IC1") (pin "Y7") (pinfunction "IO_275_Y7") (pintype "bidirectional"))
    )
    (net (code "297") (name "IO276") (class "Default")
      (node (ref "IC1") (pin "Y8") (pinfunction "IO_276_Y8") (pintype "bidirectional"))
    )
    (net (code "298") (name "IO277") (class "Default")
      (node (ref "IC1") (pin "Y10") (pinfunction "IO_277_Y10") (pintype "bidirectional"))
    )
    (net (code "299") (name "IO278") (class "Default")
      (node (ref "IC1") (pin "Y13") (pinfunction "IO_278_Y13") (pintype "bidirectional"))
    )
    (net (code "300") (name "IO279") (class "Default")
      (node (ref "IC1") (pin "Y17") (pinfunction "IO_279_Y17") (pintype "bidirectional"))
    )
    (net (code "301") (name "IO280") (class "Default")
      (node (ref "IC1") (pin "Y21") (pinfunction "IO_280_Y21") (pintype "bidirectional"))
    )
    (net (code "302") (name "IO281") (class "Default")
      (node (ref "IC1") (pin "Y22") (pinfunction "IO_281_Y22") (pintype "bidirectional"))
    )
    (net (code "303") (name "IO282") (class "Default")
      (node (ref "IC1") (pin "AA1") (pinfunction "IO_282_AA1") (pintype "bidirectional"))
    )
    (net (code "304") (name "IO283") (class "Default")
      (node (ref "IC1") (pin "AA3") (pinfunction "IO_283_AA3") (pintype "bidirectional"))
    )
    (net (code "305") (name "IO284") (class "Default")
      (node (ref "IC1") (pin "AA4") (pinfunction "IO_284_AA4") (pintype "bidirectional"))
    )
    (net (code "306") (name "IO285") (class "Default")
      (node (ref "IC1") (pin "AA5") (pinfunction "IO_285_AA5") (pintype "bidirectional"))
    )
    (net (code "307") (name "IO286") (class "Default")
      (node (ref "IC1") (pin "AA7") (pinfunction "IO_286_AA7") (pintype "bidirectional"))
    )
    (net (code "308") (name "IO287") (class "Default")
      (node (ref "IC1") (pin "AA8") (pinfunction "IO_287_AA8") (pintype "bidirectional"))
    )
    (net (code "309") (name "IO288") (class "Default")
      (node (ref "IC1") (pin "AA9") (pinfunction "IO_288_AA9") (pintype "bidirectional"))
    )
    (net (code "310") (name "IO289") (class "Default")
      (node (ref "IC1") (pin "AA10") (pinfunction "IO_289_AA10") (pintype "bidirectional"))
    )
    (net (code "311") (name "IO290") (class "Default")
      (node (ref "IC1") (pin "AA13") (pinfunction "IO_290_AA13") (pintype "bidirectional"))
    )
    (net (code "312") (name "IO291") (class "Default")
      (node (ref "IC1") (pin "AA14") (pinfunction "IO_291_AA14") (pintype "bidirectional"))
    )
    (net (code "313") (name "IO292") (class "Default")
      (node (ref "IC1") (pin "AA15") (pinfunction "IO_292_AA15") (pintype "bidirectional"))
    )
    (net (code "314") (name "IO293") (class "Default")
      (node (ref "IC1") (pin "AA16") (pinfunction "IO_293_AA16") (pintype "bidirectional"))
    )
    (net (code "315") (name "IO294") (class "Default")
      (node (ref "IC1") (pin "AA17") (pinfunction "IO_294_AA17") (pintype "bidirectional"))
    )
    (net (code "316") (name "IO295") (class "Default")
      (node (ref "IC1") (pin "AA18") (pinfunction "IO_295_AA18") (pintype "bidirectional"))
    )
    (net (code "317") (name "IO296") (class "Default")
      (node (ref "IC1") (pin "AA19") (pinfunction "IO_296_AA19") (pintype "bidirectional"))
    )
    (net (code "318") (name "IO297") (class "Default")
      (node (ref "IC1") (pin "AA20") (pinfunction "IO_297_AA20") (pintype "bidirectional"))
    )
    (net (code "319") (name "IO298") (class "Default")
      (node (ref "IC1") (pin "AA21") (pinfunction "IO_298_AA21") (pintype "bidirectional"))
    )
    (net (code "320") (name "IO299") (class "Default")
      (node (ref "IC1") (pin "AB3") (pinfunction "IO_299_AB3") (pintype "bidirectional"))
    )
    (net (code "321") (name "IO300") (class "Default")
      (node (ref "IC1") (pin "AB4") (pinfunction "IO_300_AB4") (pintype "bidirectional"))
    )
    (net (code "322") (name "IO301") (class "Default")
      (node (ref "IC1") (pin "AB5") (pinfunction "IO_301_AB5") (pintype "bidirectional"))
    )
    (net (code "323") (name "IO302") (class "Default")
      (node (ref "IC1") (pin "AB7") (pinfunction "IO_302_AB7") (pintype "bidirectional"))
    )
    (net (code "324") (name "IO303") (class "Default")
      (node (ref "IC1") (pin "AB8") (pinfunction "IO_303_AB8") (pintype "bidirectional"))
    )
    (net (code "325") (name "IO304") (class "Default")
      (node (ref "IC1") (pin "AB9") (pinfunction "IO_304_AB9") (pintype "bidirectional"))
    )
    (net (code "326") (name "IO305") (class "Default")
      (node (ref "IC1") (pin "AB10") (pinfunction "IO_305_AB10") (pintype "bidirectional"))
    )
    (net (code "327") (name "IO306") (class "Default")
      (node (ref "IC1") (pin "AB13") (pinfunction "IO_306_AB13") (pintype "bidirectional"))
    )
    (net (code "328") (name "IO307") (class "Default")
      (node (ref "IC1") (pin "AB14") (pinfunction "IO_307_AB14") (pintype "bidirectional"))
    )
    (net (code "329") (name "IO308") (class "Default")
      (node (ref "IC1") (pin "AB15") (pinfunction "IO_308_AB15") (pintype "bidirectional"))
    )
    (net (code "330") (name "IO309") (class "Default")
      (node (ref "IC1") (pin "AB16") (pinfunction "IO_309_AB16") (pintype "bidirectional"))
    )
    (net (code "331") (name "IO310") (class "Default")
      (node (ref "IC1") (pin "AB17") (pinfunction "IO_310_AB17") (pintype "bidirectional"))
    )
    (net (code "332") (name "IO311") (class "Default")
      (node (ref "IC1") (pin "AB18") (pinfunction "IO_311_AB18") (pintype "bidirectional"))
    )
    (net (code "333") (name "IO312") (class "Default")
      (node (ref "IC1") (pin "AB19") (pinfunction "IO_312_AB19") (pintype "bidirectional"))
    )
    (net (code "334") (name "IO313") (class "Default")
      (node (ref "IC1") (pin "AB20") (pinfunction "IO_313_AB20") (pintype "bidirectional"))
    )
    (net (code "335") (name "MSEL0") (class "Default")
      (node (ref "IC1") (pin "M17") (pinfunction "MSEL0_M17") (pintype "bidirectional"))
      (node (ref "R6") (pin "P$1") (pinfunction "P$1_P$1") (pintype "bidirectional"))
    )
    (net (code "336") (name "MSEL1") (class "Default")
      (node (ref "IC1") (pin "L18") (pinfunction "MSEL1_L18") (pintype "bidirectional"))
      (node (ref "R7") (pin "P$1") (pinfunction "P$1_P$1") (pintype "bidirectional"))
    )
    (net (code "337") (name "MSEL2") (class "Default")
      (node (ref "IC1") (pin "L17") (pinfunction "MSEL2_L17") (pintype "bidirectional"))
      (node (ref "R8") (pin "P$1") (pinfunction "P$1_P$1") (pintype "bidirectional"))
    )
    (net (code "338") (name "MSEL3") (class "Default")
      (node (ref "IC1") (pin "K20") (pinfunction "MSEL3_K20") (pintype "bidirectional"))
      (node (ref "R9") (pin "P$1") (pinfunction "P$1_P$1") (pintype "bidirectional"))
    )
    (net (code "339") (name "NCE") (class "Default")
      (node (ref "IC1") (pin "L3") (pinfunction "NCE_L3") (pintype "bidirectional"))
      (node (ref "R4") (pin "P$1") (pinfunction "P$1_P$1") (pintype "bidirectional"))
    )
    (net (code "340") (name "NCONFIG") (class "Default")
      (node (ref "IC1") (pin "K5") (pinfunction "NCONFIG_K5") (pintype "bidirectional"))
      (node (ref "R2") (pin "P$1") (pinfunction "P$1_P$1") (pintype "bidirectional"))
      (node (ref "SW1") (pin "2") (pinfunction "A1_2") (pintype "bidirectional"))
    )
    (net (code "341") (name "NCSO") (class "Default")
      (node (ref "IC1") (pin "E2") (pinfunction "IO_65_E2") (pintype "bidirectional"))
      (node (ref "IC2") (pin "1") (pinfunction "NCS_1") (pintype "bidirectional"))
      (node (ref "JP54") (pin "1") (pinfunction "1_1") (pintype "passive"))
    )
    (net (code "342") (name "NSTATUS") (class "Default")
      (node (ref "IC1") (pin "K6") (pinfunction "NSTATUS_K6") (pintype "bidirectional"))
      (node (ref "R5") (pin "P$1") (pinfunction "P$1_P$1") (pintype "bidirectional"))
    )
    (net (code "343") (name "Net-(LED33-PadA)") (class "Default")
      (node (ref "LED33") (pin "A") (pinfunction "A_A") (pintype "passive"))
      (node (ref "R45") (pin "P$2") (pinfunction "P$2_P$2") (pintype "bidirectional"))
    )
    (net (code "344") (name "Net-(LED34-PadA)") (class "Default")
      (node (ref "LED34") (pin "A") (pinfunction "A_A") (pintype "passive"))
      (node (ref "R44") (pin "P$2") (pinfunction "P$2_P$2") (pintype "bidirectional"))
    )
    (net (code "345") (name "Net-(LED35-PadA)") (class "Default")
      (node (ref "LED35") (pin "A") (pinfunction "A_A") (pintype "passive"))
      (node (ref "R43") (pin "P$2") (pinfunction "P$2_P$2") (pintype "bidirectional"))
    )
    (net (code "346") (name "Net-(LED36-PadA)") (class "Default")
      (node (ref "LED36") (pin "A") (pinfunction "A_A") (pintype "passive"))
      (node (ref "R42") (pin "P$2") (pinfunction "P$2_P$2") (pintype "bidirectional"))
    )
    (net (code "347") (name "Net-(LED37-PadA)") (class "Default")
      (node (ref "LED37") (pin "A") (pinfunction "A_A") (pintype "passive"))
      (node (ref "R41") (pin "P$2") (pinfunction "P$2_P$2") (pintype "bidirectional"))
    )
    (net (code "348") (name "Net-(LED38-PadA)") (class "Default")
      (node (ref "LED38") (pin "A") (pinfunction "A_A") (pintype "passive"))
      (node (ref "R40") (pin "P$2") (pinfunction "P$2_P$2") (pintype "bidirectional"))
    )
    (net (code "349") (name "Net-(LED39-PadA)") (class "Default")
      (node (ref "LED39") (pin "A") (pinfunction "A_A") (pintype "passive"))
      (node (ref "R39") (pin "P$2") (pinfunction "P$2_P$2") (pintype "bidirectional"))
    )
    (net (code "350") (name "Net-(LED40-PadA)") (class "Default")
      (node (ref "LED40") (pin "A") (pinfunction "A_A") (pintype "passive"))
      (node (ref "R38") (pin "P$2") (pinfunction "P$2_P$2") (pintype "bidirectional"))
    )
    (net (code "351") (name "TCK") (class "Default")
      (node (ref "IC1") (pin "L2") (pinfunction "TCK_L2") (pintype "bidirectional"))
      (node (ref "J1") (pin "1") (pinfunction "1_1") (pintype "passive"))
    )
    (net (code "352") (name "TDI") (class "Default")
      (node (ref "IC1") (pin "L5") (pinfunction "TDI_L5") (pintype "bidirectional"))
      (node (ref "J1") (pin "9") (pinfunction "9_9") (pintype "passive"))
    )
    (net (code "353") (name "TDO") (class "Default")
      (node (ref "IC1") (pin "L4") (pinfunction "TDO_L4") (pintype "bidirectional"))
      (node (ref "J1") (pin "3") (pinfunction "3_3") (pintype "passive"))
    )
    (net (code "354") (name "TMS") (class "Default")
      (node (ref "IC1") (pin "L1") (pinfunction "TMS_L1") (pintype "bidirectional"))
      (node (ref "J1") (pin "5") (pinfunction "5_5") (pintype "passive"))
    )
    (net (code "355") (name "VCCA") (class "Default")
      (node (ref "C26") (pin "2") (pinfunction "2_2") (pintype "passive"))
      (node (ref "IC1") (pin "F18") (pinfunction "VCCA2_F18") (pintype "bidirectional"))
      (node (ref "IC1") (pin "G6") (pinfunction "VCCA3_G6") (pintype "bidirectional"))
      (node (ref "IC1") (pin "T6") (pinfunction "VCCA1_T6") (pintype "bidirectional"))
      (node (ref "IC1") (pin "U18") (pinfunction "VCCA4_U18") (pintype "bidirectional"))
      (node (ref "R20") (pin "P$2") (pinfunction "P$2_P$2") (pintype "bidirectional"))
    )
    (net (code "356") (name "VCCINT") (class "Default")
      (node (ref "C24") (pin "2") (pinfunction "2_2") (pintype "passive"))
      (node (ref "IC1") (pin "G12") (pinfunction "VCCINT_1_G12") (pintype "bidirectional"))
      (node (ref "IC1") (pin "H9") (pinfunction "VCCINT_2_H9") (pintype "bidirectional"))
      (node (ref "IC1") (pin "J10") (pinfunction "VCCINT_3_J10") (pintype "bidirectional"))
      (node (ref "IC1") (pin "J11") (pinfunction "VCCINT_4_J11") (pintype "bidirectional"))
      (node (ref "IC1") (pin "J12") (pinfunction "VCCINT_5_J12") (pintype "bidirectional"))
      (node (ref "IC1") (pin "J13") (pinfunction "VCCINT_6_J13") (pintype "bidirectional"))
      (node (ref "IC1") (pin "J14") (pinfunction "VCCINT_7_J14") (pintype "bidirectional"))
      (node (ref "IC1") (pin "J16") (pinfunction "VCCINT_8_J16") (pintype "bidirectional"))
      (node (ref "IC1") (pin "K14") (pinfunction "VCCINT_10_K14") (pintype "bidirectional"))
      (node (ref "IC1") (pin "K15") (pinfunction "VCCINT_11_K15") (pintype "bidirectional"))
      (node (ref "IC1") (pin "K9") (pinfunction "VCCINT_9_K9") (pintype "bidirectional"))
      (node (ref "IC1") (pin "L14") (pinfunction "VCCINT_13_L14") (pintype "bidirectional"))
      (node (ref "IC1") (pin "L16") (pinfunction "VCCINT_14_L16") (pintype "bidirectional"))
      (node (ref "IC1") (pin "L9") (pinfunction "VCCINT_12_L9") (pintype "bidirectional"))
      (node (ref "IC1") (pin "M14") (pinfunction "VCCINT_16_M14") (pintype "bidirectional"))
      (node (ref "IC1") (pin "M15") (pinfunction "VCCINT_17_M15") (pintype "bidirectional"))
      (node (ref "IC1") (pin "M9") (pinfunction "VCCINT_15_M9") (pintype "bidirectional"))
      (node (ref "IC1") (pin "N14") (pinfunction "VCCINT_19_N14") (pintype "bidirectional"))
      (node (ref "IC1") (pin "N9") (pinfunction "VCCINT_18_N9") (pintype "bidirectional"))
      (node (ref "IC1") (pin "P10") (pinfunction "VCCINT_21_P10") (pintype "bidirectional"))
      (node (ref "IC1") (pin "P11") (pinfunction "VCCINT_22_P11") (pintype "bidirectional"))
      (node (ref "IC1") (pin "P12") (pinfunction "VCCINT_23_P12") (pintype "bidirectional"))
      (node (ref "IC1") (pin "P13") (pinfunction "VCCINT_24_P13") (pintype "bidirectional"))
      (node (ref "IC1") (pin "P14") (pinfunction "VCCINT_25_P14") (pintype "bidirectional"))
      (node (ref "IC1") (pin "P9") (pinfunction "VCCINT_20_P9") (pintype "bidirectional"))
      (node (ref "IC1") (pin "R10") (pinfunction "VCCINT_27_R10") (pintype "bidirectional"))
      (node (ref "IC1") (pin "R12") (pinfunction "VCCINT_28_R12") (pintype "bidirectional"))
      (node (ref "IC1") (pin "R8") (pinfunction "VCCINT_26_R8") (pintype "bidirectional"))
      (node (ref "R18") (pin "P$2") (pinfunction "P$2_P$2") (pintype "bidirectional"))
    )
    (net (code "357") (name "VCCIO") (class "Default")
      (node (ref "C16") (pin "2") (pinfunction "2_2") (pintype "passive"))
      (node (ref "C17") (pin "2") (pinfunction "2_2") (pintype "passive"))
      (node (ref "C18") (pin "2") (pinfunction "2_2") (pintype "passive"))
      (node (ref "C19") (pin "2") (pinfunction "2_2") (pintype "passive"))
      (node (ref "C20") (pin "2") (pinfunction "2_2") (pintype "passive"))
      (node (ref "C21") (pin "2") (pinfunction "2_2") (pintype "passive"))
      (node (ref "C22") (pin "2") (pinfunction "2_2") (pintype "passive"))
      (node (ref "C23") (pin "2") (pinfunction "2_2") (pintype "passive"))
      (node (ref "IC1") (pin "A2") (pinfunction "VCCIO8_1_A2") (pintype "bidirectional"))
      (node (ref "IC1") (pin "A21") (pinfunction "VCCIO7_1_A21") (pintype "bidirectional"))
      (node (ref "IC1") (pin "AA6") (pinfunction "VCCIO3_4_AA6") (pintype "bidirectional"))
      (node (ref "IC1") (pin "AB2") (pinfunction "VCCIO3_5_AB2") (pintype "bidirectional"))
      (node (ref "IC1") (pin "AB21") (pinfunction "VCCIO4_5_AB21") (pintype "bidirectional"))
      (node (ref "IC1") (pin "D11") (pinfunction "VCCIO8_4_D11") (pintype "bidirectional"))
      (node (ref "IC1") (pin "D12") (pinfunction "VCCIO7_2_D12") (pintype "bidirectional"))
      (node (ref "IC1") (pin "D14") (pinfunction "VCCIO7_3_D14") (pintype "bidirectional"))
      (node (ref "IC1") (pin "D16") (pinfunction "VCCIO7_4_D16") (pintype "bidirectional"))
      (node (ref "IC1") (pin "D18") (pinfunction "VCCIO7_5_D18") (pintype "bidirectional"))
      (node (ref "IC1") (pin "D4") (pinfunction "VCCIO1_1_D4") (pintype "bidirectional"))
      (node (ref "IC1") (pin "D5") (pinfunction "VCCIO8_2_D5") (pintype "bidirectional"))
      (node (ref "IC1") (pin "D9") (pinfunction "VCCIO8_3_D9") (pintype "bidirectional"))
      (node (ref "IC1") (pin "E19") (pinfunction "VCCIO6_1_E19") (pintype "bidirectional"))
      (node (ref "IC1") (pin "E8") (pinfunction "VCCIO8_5_E8") (pintype "bidirectional"))
      (node (ref "IC1") (pin "F4") (pinfunction "VCCIO1_2_F4") (pintype "bidirectional"))
      (node (ref "IC1") (pin "G19") (pinfunction "VCCIO6_2_G19") (pintype "bidirectional"))
      (node (ref "IC1") (pin "H4") (pinfunction "VCCIO1_3_H4") (pintype "bidirectional"))
      (node (ref "IC1") (pin "J20") (pinfunction "VCCIO6_3_J20") (pintype "bidirectional"))
      (node (ref "IC1") (pin "K4") (pinfunction "VCCIO1_4_K4") (pintype "bidirectional"))
      (node (ref "IC1") (pin "L19") (pinfunction "VCCIO6_4_L19") (pintype "bidirectional"))
      (node (ref "IC1") (pin "N4") (pinfunction "VCCIO2_1_N4") (pintype "bidirectional"))
      (node (ref "IC1") (pin "P18") (pinfunction "VCCIO5_1_P18") (pintype "bidirectional"))
      (node (ref "IC1") (pin "R4") (pinfunction "VCCIO2_2_R4") (pintype "bidirectional"))
      (node (ref "IC1") (pin "T19") (pinfunction "VCCIO5_2_T19") (pintype "bidirectional"))
      (node (ref "IC1") (pin "U4") (pinfunction "VCCIO2_3_U4") (pintype "bidirectional"))
      (node (ref "IC1") (pin "V19") (pinfunction "VCCIO5_3_V19") (pintype "bidirectional"))
      (node (ref "IC1") (pin "W11") (pinfunction "VCCIO3_3_W11") (pintype "bidirectional"))
      (node (ref "IC1") (pin "W12") (pinfunction "VCCIO4_1_W12") (pintype "bidirectional"))
      (node (ref "IC1") (pin "W16") (pinfunction "VCCIO4_2_W16") (pintype "bidirectional"))
      (node (ref "IC1") (pin "W18") (pinfunction "VCCIO4_3_W18") (pintype "bidirectional"))
      (node (ref "IC1") (pin "W4") (pinfunction "VCCIO2_4_W4") (pintype "bidirectional"))
      (node (ref "IC1") (pin "W5") (pinfunction "VCCIO3_1_W5") (pintype "bidirectional"))
      (node (ref "IC1") (pin "W9") (pinfunction "VCCIO3_2_W9") (pintype "bidirectional"))
      (node (ref "IC1") (pin "Y14") (pinfunction "VCCIO4_4_Y14") (pintype "bidirectional"))
      (node (ref "IC1") (pin "Y19") (pinfunction "VCCIO5_4_Y19") (pintype "bidirectional"))
      (node (ref "R17") (pin "P$2") (pinfunction "P$2_P$2") (pintype "bidirectional"))
    )
    (net (code "358") (name "VCCPLL") (class "Default")
      (node (ref "C25") (pin "2") (pinfunction "2_2") (pintype "passive"))
      (node (ref "IC1") (pin "E17") (pinfunction "VCCD_PLL2_E17") (pintype "bidirectional"))
      (node (ref "IC1") (pin "F6") (pinfunction "VCCD_PLL3_F6") (pintype "bidirectional"))
      (node (ref "IC1") (pin "U6") (pinfunction "VCCD_PLL1_U6") (pintype "bidirectional"))
      (node (ref "IC1") (pin "V17") (pinfunction "VCCD_PLL4_V17") (pintype "bidirectional"))
      (node (ref "R19") (pin "P$2") (pinfunction "P$2_P$2") (pintype "bidirectional"))
    )
    (net (code "359") (name "unconnected-(J1-Pad6)") (class "Default")
      (node (ref "J1") (pin "6") (pinfunction "6_6") (pintype "passive"))
    )
    (net (code "360") (name "unconnected-(J1-Pad7)") (class "Default")
      (node (ref "J1") (pin "7") (pinfunction "7_7") (pintype "passive"))
    )
    (net (code "361") (name "unconnected-(J1-Pad8)") (class "Default")
      (node (ref "J1") (pin "8") (pinfunction "8_8") (pintype "passive"))
    )
    (net (code "362") (name "unconnected-(SW1-A0-Pad1)") (class "Default")
      (node (ref "SW1") (pin "1") (pinfunction "A0_1") (pintype "bidirectional"))
    )
    (net (code "363") (name "unconnected-(SW1-B0-Pad3)") (class "Default")
      (node (ref "SW1") (pin "3") (pinfunction "B0_3") (pintype "bidirectional"))
    )
    (net (code "364") (name "unconnected-(SW2-A0-Pad1)") (class "Default")
      (node (ref "SW2") (pin "1") (pinfunction "A0_1") (pintype "bidirectional"))
    )
    (net (code "365") (name "unconnected-(SW2-B0-Pad3)") (class "Default")
      (node (ref "SW2") (pin "3") (pinfunction "B0_3") (pintype "bidirectional"))
    )
    (net (code "366") (name "unconnected-(Y1-EN-Pad1)") (class "Default")
      (node (ref "Y1") (pin "1") (pinfunction "EN_1") (pintype "bidirectional"))
    )
  )
)
